# Matrix_True.net
KiCad netlist of a schematic drawn in EAGLE
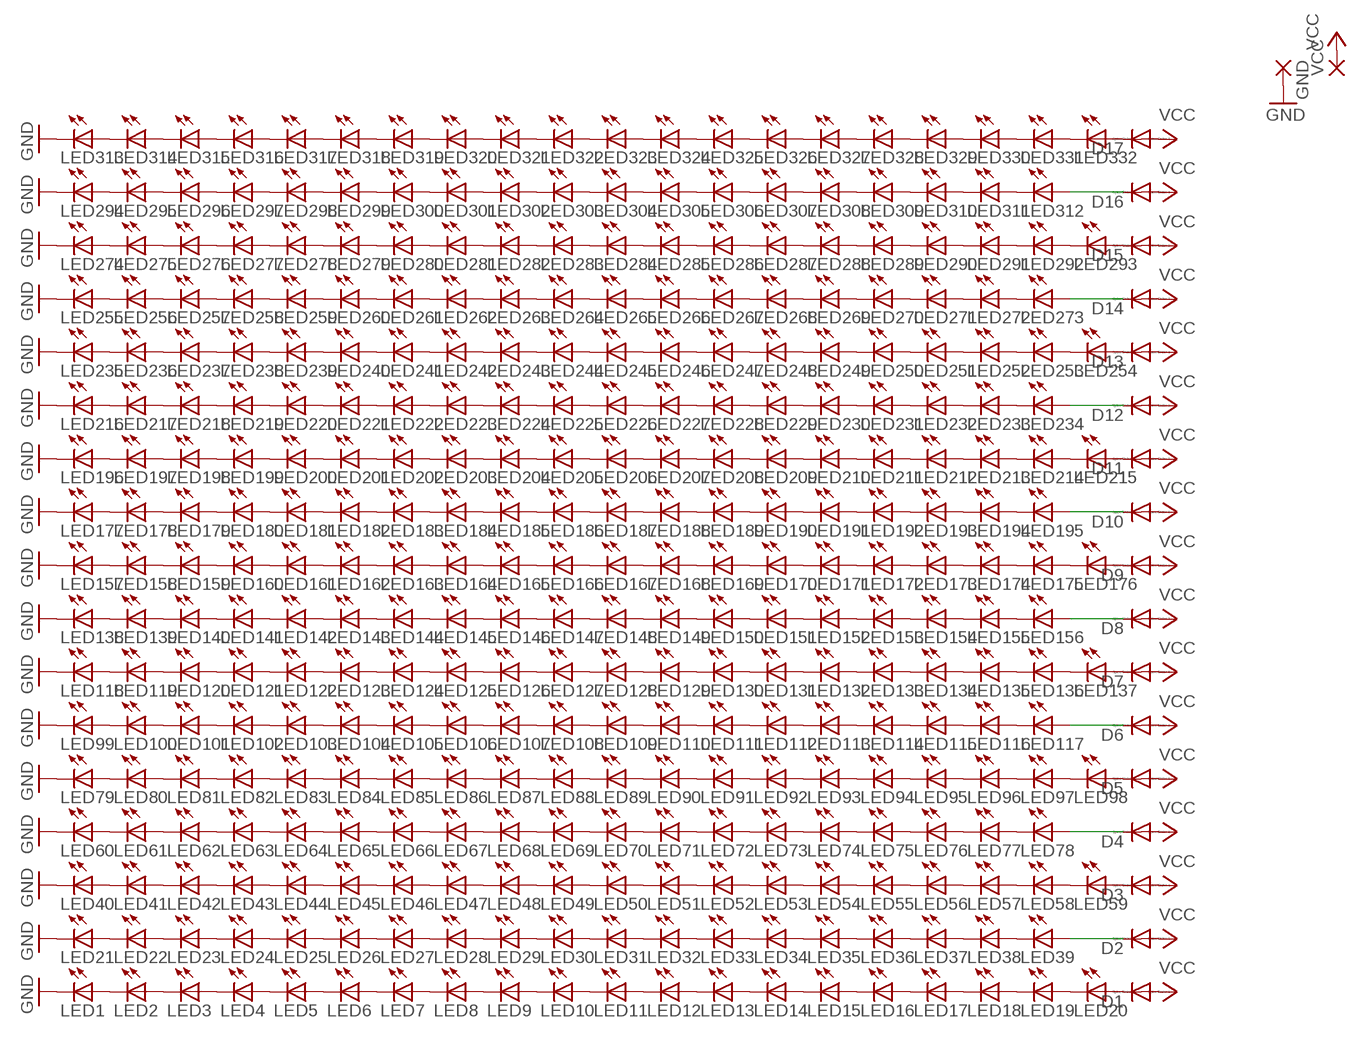
[diagram p0: schematic, sheet 1]

(export (version "E")
  (design (tool "Eeschema 10.0.6"))
  (components
    (comp (ref "D1")
      (value "DIODE-SOD123")
      (footprint "eagle-import:SOD123")
      (libsource (lib "eagle-import") (part "DIODE-SOD123"))
    )
    (comp (ref "D2")
      (value "DIODE-SOD123")
      (footprint "eagle-import:SOD123")
      (libsource (lib "eagle-import") (part "DIODE-SOD123"))
    )
    (comp (ref "D3")
      (value "DIODE-SOD123")
      (footprint "eagle-import:SOD123")
      (libsource (lib "eagle-import") (part "DIODE-SOD123"))
    )
    (comp (ref "D4")
      (value "DIODE-SOD123")
      (footprint "eagle-import:SOD123")
      (libsource (lib "eagle-import") (part "DIODE-SOD123"))
    )
    (comp (ref "D5")
      (value "DIODE-SOD123")
      (footprint "eagle-import:SOD123")
      (libsource (lib "eagle-import") (part "DIODE-SOD123"))
    )
    (comp (ref "D6")
      (value "DIODE-SOD123")
      (footprint "eagle-import:SOD123")
      (libsource (lib "eagle-import") (part "DIODE-SOD123"))
    )
    (comp (ref "D7")
      (value "DIODE-SOD123")
      (footprint "eagle-import:SOD123")
      (libsource (lib "eagle-import") (part "DIODE-SOD123"))
    )
    (comp (ref "D8")
      (value "DIODE-SOD123")
      (footprint "eagle-import:SOD123")
      (libsource (lib "eagle-import") (part "DIODE-SOD123"))
    )
    (comp (ref "D9")
      (value "DIODE-SOD123")
      (footprint "eagle-import:SOD123")
      (libsource (lib "eagle-import") (part "DIODE-SOD123"))
    )
    (comp (ref "D10")
      (value "DIODE-SOD123")
      (footprint "eagle-import:SOD123")
      (libsource (lib "eagle-import") (part "DIODE-SOD123"))
    )
    (comp (ref "D11")
      (value "DIODE-SOD123")
      (footprint "eagle-import:SOD123")
      (libsource (lib "eagle-import") (part "DIODE-SOD123"))
    )
    (comp (ref "D12")
      (value "DIODE-SOD123")
      (footprint "eagle-import:SOD123")
      (libsource (lib "eagle-import") (part "DIODE-SOD123"))
    )
    (comp (ref "D13")
      (value "DIODE-SOD123")
      (footprint "eagle-import:SOD123")
      (libsource (lib "eagle-import") (part "DIODE-SOD123"))
    )
    (comp (ref "D14")
      (value "DIODE-SOD123")
      (footprint "eagle-import:SOD123")
      (libsource (lib "eagle-import") (part "DIODE-SOD123"))
    )
    (comp (ref "D15")
      (value "DIODE-SOD123")
      (footprint "eagle-import:SOD123")
      (libsource (lib "eagle-import") (part "DIODE-SOD123"))
    )
    (comp (ref "D16")
      (value "DIODE-SOD123")
      (footprint "eagle-import:SOD123")
      (libsource (lib "eagle-import") (part "DIODE-SOD123"))
    )
    (comp (ref "D17")
      (value "DIODE-SOD123")
      (footprint "eagle-import:SOD123")
      (libsource (lib "eagle-import") (part "DIODE-SOD123"))
    )
    (comp (ref "GND")
      (value "3,17/1,3")
      (footprint "eagle-import:3,17_1,3")
      (libsource (lib "eagle-import") (part "3,17/1,3"))
    )
    (comp (ref "LED1")
      (value "LED5MM")
      (footprint "eagle-import:LED5MM")
      (libsource (lib "eagle-import") (part "LED5MM"))
    )
    (comp (ref "LED2")
      (value "LED5MM")
      (footprint "eagle-import:LED5MM")
      (libsource (lib "eagle-import") (part "LED5MM"))
    )
    (comp (ref "LED3")
      (value "LED5MM")
      (footprint "eagle-import:LED5MM")
      (libsource (lib "eagle-import") (part "LED5MM"))
    )
    (comp (ref "LED4")
      (value "LED5MM")
      (footprint "eagle-import:LED5MM")
      (libsource (lib "eagle-import") (part "LED5MM"))
    )
    (comp (ref "LED5")
      (value "LED5MM")
      (footprint "eagle-import:LED5MM")
      (libsource (lib "eagle-import") (part "LED5MM"))
    )
    (comp (ref "LED6")
      (value "LED5MM")
      (footprint "eagle-import:LED5MM")
      (libsource (lib "eagle-import") (part "LED5MM"))
    )
    (comp (ref "LED7")
      (value "LED5MM")
      (footprint "eagle-import:LED5MM")
      (libsource (lib "eagle-import") (part "LED5MM"))
    )
    (comp (ref "LED8")
      (value "LED5MM")
      (footprint "eagle-import:LED5MM")
      (libsource (lib "eagle-import") (part "LED5MM"))
    )
    (comp (ref "LED9")
      (value "LED5MM")
      (footprint "eagle-import:LED5MM")
      (libsource (lib "eagle-import") (part "LED5MM"))
    )
    (comp (ref "LED10")
      (value "LED5MM")
      (footprint "eagle-import:LED5MM")
      (libsource (lib "eagle-import") (part "LED5MM"))
    )
    (comp (ref "LED11")
      (value "LED5MM")
      (footprint "eagle-import:LED5MM")
      (libsource (lib "eagle-import") (part "LED5MM"))
    )
    (comp (ref "LED12")
      (value "LED5MM")
      (footprint "eagle-import:LED5MM")
      (libsource (lib "eagle-import") (part "LED5MM"))
    )
    (comp (ref "LED13")
      (value "LED5MM")
      (footprint "eagle-import:LED5MM")
      (libsource (lib "eagle-import") (part "LED5MM"))
    )
    (comp (ref "LED14")
      (value "LED5MM")
      (footprint "eagle-import:LED5MM")
      (libsource (lib "eagle-import") (part "LED5MM"))
    )
    (comp (ref "LED15")
      (value "LED5MM")
      (footprint "eagle-import:LED5MM")
      (libsource (lib "eagle-import") (part "LED5MM"))
    )
    (comp (ref "LED16")
      (value "LED5MM")
      (footprint "eagle-import:LED5MM")
      (libsource (lib "eagle-import") (part "LED5MM"))
    )
    (comp (ref "LED17")
      (value "LED5MM")
      (footprint "eagle-import:LED5MM")
      (libsource (lib "eagle-import") (part "LED5MM"))
    )
    (comp (ref "LED18")
      (value "LED5MM")
      (footprint "eagle-import:LED5MM")
      (libsource (lib "eagle-import") (part "LED5MM"))
    )
    (comp (ref "LED19")
      (value "LED5MM")
      (footprint "eagle-import:LED5MM")
      (libsource (lib "eagle-import") (part "LED5MM"))
    )
    (comp (ref "LED20")
      (value "LED5MM")
      (footprint "eagle-import:LED5MM")
      (libsource (lib "eagle-import") (part "LED5MM"))
    )
    (comp (ref "LED21")
      (value "LED5MM")
      (footprint "eagle-import:LED5MM")
      (libsource (lib "eagle-import") (part "LED5MM"))
    )
    (comp (ref "LED22")
      (value "LED5MM")
      (footprint "eagle-import:LED5MM")
      (libsource (lib "eagle-import") (part "LED5MM"))
    )
    (comp (ref "LED23")
      (value "LED5MM")
      (footprint "eagle-import:LED5MM")
      (libsource (lib "eagle-import") (part "LED5MM"))
    )
    (comp (ref "LED24")
      (value "LED5MM")
      (footprint "eagle-import:LED5MM")
      (libsource (lib "eagle-import") (part "LED5MM"))
    )
    (comp (ref "LED25")
      (value "LED5MM")
      (footprint "eagle-import:LED5MM")
      (libsource (lib "eagle-import") (part "LED5MM"))
    )
    (comp (ref "LED26")
      (value "LED5MM")
      (footprint "eagle-import:LED5MM")
      (libsource (lib "eagle-import") (part "LED5MM"))
    )
    (comp (ref "LED27")
      (value "LED5MM")
      (footprint "eagle-import:LED5MM")
      (libsource (lib "eagle-import") (part "LED5MM"))
    )
    (comp (ref "LED28")
      (value "LED5MM")
      (footprint "eagle-import:LED5MM")
      (libsource (lib "eagle-import") (part "LED5MM"))
    )
    (comp (ref "LED29")
      (value "LED5MM")
      (footprint "eagle-import:LED5MM")
      (libsource (lib "eagle-import") (part "LED5MM"))
    )
    (comp (ref "LED30")
      (value "LED5MM")
      (footprint "eagle-import:LED5MM")
      (libsource (lib "eagle-import") (part "LED5MM"))
    )
    (comp (ref "LED31")
      (value "LED5MM")
      (footprint "eagle-import:LED5MM")
      (libsource (lib "eagle-import") (part "LED5MM"))
    )
    (comp (ref "LED32")
      (value "LED5MM")
      (footprint "eagle-import:LED5MM")
      (libsource (lib "eagle-import") (part "LED5MM"))
    )
    (comp (ref "LED33")
      (value "LED5MM")
      (footprint "eagle-import:LED5MM")
      (libsource (lib "eagle-import") (part "LED5MM"))
    )
    (comp (ref "LED34")
      (value "LED5MM")
      (footprint "eagle-import:LED5MM")
      (libsource (lib "eagle-import") (part "LED5MM"))
    )
    (comp (ref "LED35")
      (value "LED5MM")
      (footprint "eagle-import:LED5MM")
      (libsource (lib "eagle-import") (part "LED5MM"))
    )
    (comp (ref "LED36")
      (value "LED5MM")
      (footprint "eagle-import:LED5MM")
      (libsource (lib "eagle-import") (part "LED5MM"))
    )
    (comp (ref "LED37")
      (value "LED5MM")
      (footprint "eagle-import:LED5MM")
      (libsource (lib "eagle-import") (part "LED5MM"))
    )
    (comp (ref "LED38")
      (value "LED5MM")
      (footprint "eagle-import:LED5MM")
      (libsource (lib "eagle-import") (part "LED5MM"))
    )
    (comp (ref "LED39")
      (value "LED5MM")
      (footprint "eagle-import:LED5MM")
      (libsource (lib "eagle-import") (part "LED5MM"))
    )
    (comp (ref "LED40")
      (value "LED5MM")
      (footprint "eagle-import:LED5MM")
      (libsource (lib "eagle-import") (part "LED5MM"))
    )
    (comp (ref "LED41")
      (value "LED5MM")
      (footprint "eagle-import:LED5MM")
      (libsource (lib "eagle-import") (part "LED5MM"))
    )
    (comp (ref "LED42")
      (value "LED5MM")
      (footprint "eagle-import:LED5MM")
      (libsource (lib "eagle-import") (part "LED5MM"))
    )
    (comp (ref "LED43")
      (value "LED5MM")
      (footprint "eagle-import:LED5MM")
      (libsource (lib "eagle-import") (part "LED5MM"))
    )
    (comp (ref "LED44")
      (value "LED5MM")
      (footprint "eagle-import:LED5MM")
      (libsource (lib "eagle-import") (part "LED5MM"))
    )
    (comp (ref "LED45")
      (value "LED5MM")
      (footprint "eagle-import:LED5MM")
      (libsource (lib "eagle-import") (part "LED5MM"))
    )
    (comp (ref "LED46")
      (value "LED5MM")
      (footprint "eagle-import:LED5MM")
      (libsource (lib "eagle-import") (part "LED5MM"))
    )
    (comp (ref "LED47")
      (value "LED5MM")
      (footprint "eagle-import:LED5MM")
      (libsource (lib "eagle-import") (part "LED5MM"))
    )
    (comp (ref "LED48")
      (value "LED5MM")
      (footprint "eagle-import:LED5MM")
      (libsource (lib "eagle-import") (part "LED5MM"))
    )
    (comp (ref "LED49")
      (value "LED5MM")
      (footprint "eagle-import:LED5MM")
      (libsource (lib "eagle-import") (part "LED5MM"))
    )
    (comp (ref "LED50")
      (value "LED5MM")
      (footprint "eagle-import:LED5MM")
      (libsource (lib "eagle-import") (part "LED5MM"))
    )
    (comp (ref "LED51")
      (value "LED5MM")
      (footprint "eagle-import:LED5MM")
      (libsource (lib "eagle-import") (part "LED5MM"))
    )
    (comp (ref "LED52")
      (value "LED5MM")
      (footprint "eagle-import:LED5MM")
      (libsource (lib "eagle-import") (part "LED5MM"))
    )
    (comp (ref "LED53")
      (value "LED5MM")
      (footprint "eagle-import:LED5MM")
      (libsource (lib "eagle-import") (part "LED5MM"))
    )
    (comp (ref "LED54")
      (value "LED5MM")
      (footprint "eagle-import:LED5MM")
      (libsource (lib "eagle-import") (part "LED5MM"))
    )
    (comp (ref "LED55")
      (value "LED5MM")
      (footprint "eagle-import:LED5MM")
      (libsource (lib "eagle-import") (part "LED5MM"))
    )
    (comp (ref "LED56")
      (value "LED5MM")
      (footprint "eagle-import:LED5MM")
      (libsource (lib "eagle-import") (part "LED5MM"))
    )
    (comp (ref "LED57")
      (value "LED5MM")
      (footprint "eagle-import:LED5MM")
      (libsource (lib "eagle-import") (part "LED5MM"))
    )
    (comp (ref "LED58")
      (value "LED5MM")
      (footprint "eagle-import:LED5MM")
      (libsource (lib "eagle-import") (part "LED5MM"))
    )
    (comp (ref "LED59")
      (value "LED5MM")
      (footprint "eagle-import:LED5MM")
      (libsource (lib "eagle-import") (part "LED5MM"))
    )
    (comp (ref "LED60")
      (value "LED5MM")
      (footprint "eagle-import:LED5MM")
      (libsource (lib "eagle-import") (part "LED5MM"))
    )
    (comp (ref "LED61")
      (value "LED5MM")
      (footprint "eagle-import:LED5MM")
      (libsource (lib "eagle-import") (part "LED5MM"))
    )
    (comp (ref "LED62")
      (value "LED5MM")
      (footprint "eagle-import:LED5MM")
      (libsource (lib "eagle-import") (part "LED5MM"))
    )
    (comp (ref "LED63")
      (value "LED5MM")
      (footprint "eagle-import:LED5MM")
      (libsource (lib "eagle-import") (part "LED5MM"))
    )
    (comp (ref "LED64")
      (value "LED5MM")
      (footprint "eagle-import:LED5MM")
      (libsource (lib "eagle-import") (part "LED5MM"))
    )
    (comp (ref "LED65")
      (value "LED5MM")
      (footprint "eagle-import:LED5MM")
      (libsource (lib "eagle-import") (part "LED5MM"))
    )
    (comp (ref "LED66")
      (value "LED5MM")
      (footprint "eagle-import:LED5MM")
      (libsource (lib "eagle-import") (part "LED5MM"))
    )
    (comp (ref "LED67")
      (value "LED5MM")
      (footprint "eagle-import:LED5MM")
      (libsource (lib "eagle-import") (part "LED5MM"))
    )
    (comp (ref "LED68")
      (value "LED5MM")
      (footprint "eagle-import:LED5MM")
      (libsource (lib "eagle-import") (part "LED5MM"))
    )
    (comp (ref "LED69")
      (value "LED5MM")
      (footprint "eagle-import:LED5MM")
      (libsource (lib "eagle-import") (part "LED5MM"))
    )
    (comp (ref "LED70")
      (value "LED5MM")
      (footprint "eagle-import:LED5MM")
      (libsource (lib "eagle-import") (part "LED5MM"))
    )
    (comp (ref "LED71")
      (value "LED5MM")
      (footprint "eagle-import:LED5MM")
      (libsource (lib "eagle-import") (part "LED5MM"))
    )
    (comp (ref "LED72")
      (value "LED5MM")
      (footprint "eagle-import:LED5MM")
      (libsource (lib "eagle-import") (part "LED5MM"))
    )
    (comp (ref "LED73")
      (value "LED5MM")
      (footprint "eagle-import:LED5MM")
      (libsource (lib "eagle-import") (part "LED5MM"))
    )
    (comp (ref "LED74")
      (value "LED5MM")
      (footprint "eagle-import:LED5MM")
      (libsource (lib "eagle-import") (part "LED5MM"))
    )
    (comp (ref "LED75")
      (value "LED5MM")
      (footprint "eagle-import:LED5MM")
      (libsource (lib "eagle-import") (part "LED5MM"))
    )
    (comp (ref "LED76")
      (value "LED5MM")
      (footprint "eagle-import:LED5MM")
      (libsource (lib "eagle-import") (part "LED5MM"))
    )
    (comp (ref "LED77")
      (value "LED5MM")
      (footprint "eagle-import:LED5MM")
      (libsource (lib "eagle-import") (part "LED5MM"))
    )
    (comp (ref "LED78")
      (value "LED5MM")
      (footprint "eagle-import:LED5MM")
      (libsource (lib "eagle-import") (part "LED5MM"))
    )
    (comp (ref "LED79")
      (value "LED5MM")
      (footprint "eagle-import:LED5MM")
      (libsource (lib "eagle-import") (part "LED5MM"))
    )
    (comp (ref "LED80")
      (value "LED5MM")
      (footprint "eagle-import:LED5MM")
      (libsource (lib "eagle-import") (part "LED5MM"))
    )
    (comp (ref "LED81")
      (value "LED5MM")
      (footprint "eagle-import:LED5MM")
      (libsource (lib "eagle-import") (part "LED5MM"))
    )
    (comp (ref "LED82")
      (value "LED5MM")
      (footprint "eagle-import:LED5MM")
      (libsource (lib "eagle-import") (part "LED5MM"))
    )
    (comp (ref "LED83")
      (value "LED5MM")
      (footprint "eagle-import:LED5MM")
      (libsource (lib "eagle-import") (part "LED5MM"))
    )
    (comp (ref "LED84")
      (value "LED5MM")
      (footprint "eagle-import:LED5MM")
      (libsource (lib "eagle-import") (part "LED5MM"))
    )
    (comp (ref "LED85")
      (value "LED5MM")
      (footprint "eagle-import:LED5MM")
      (libsource (lib "eagle-import") (part "LED5MM"))
    )
    (comp (ref "LED86")
      (value "LED5MM")
      (footprint "eagle-import:LED5MM")
      (libsource (lib "eagle-import") (part "LED5MM"))
    )
    (comp (ref "LED87")
      (value "LED5MM")
      (footprint "eagle-import:LED5MM")
      (libsource (lib "eagle-import") (part "LED5MM"))
    )
    (comp (ref "LED88")
      (value "LED5MM")
      (footprint "eagle-import:LED5MM")
      (libsource (lib "eagle-import") (part "LED5MM"))
    )
    (comp (ref "LED89")
      (value "LED5MM")
      (footprint "eagle-import:LED5MM")
      (libsource (lib "eagle-import") (part "LED5MM"))
    )
    (comp (ref "LED90")
      (value "LED5MM")
      (footprint "eagle-import:LED5MM")
      (libsource (lib "eagle-import") (part "LED5MM"))
    )
    (comp (ref "LED91")
      (value "LED5MM")
      (footprint "eagle-import:LED5MM")
      (libsource (lib "eagle-import") (part "LED5MM"))
    )
    (comp (ref "LED92")
      (value "LED5MM")
      (footprint "eagle-import:LED5MM")
      (libsource (lib "eagle-import") (part "LED5MM"))
    )
    (comp (ref "LED93")
      (value "LED5MM")
      (footprint "eagle-import:LED5MM")
      (libsource (lib "eagle-import") (part "LED5MM"))
    )
    (comp (ref "LED94")
      (value "LED5MM")
      (footprint "eagle-import:LED5MM")
      (libsource (lib "eagle-import") (part "LED5MM"))
    )
    (comp (ref "LED95")
      (value "LED5MM")
      (footprint "eagle-import:LED5MM")
      (libsource (lib "eagle-import") (part "LED5MM"))
    )
    (comp (ref "LED96")
      (value "LED5MM")
      (footprint "eagle-import:LED5MM")
      (libsource (lib "eagle-import") (part "LED5MM"))
    )
    (comp (ref "LED97")
      (value "LED5MM")
      (footprint "eagle-import:LED5MM")
      (libsource (lib "eagle-import") (part "LED5MM"))
    )
    (comp (ref "LED98")
      (value "LED5MM")
      (footprint "eagle-import:LED5MM")
      (libsource (lib "eagle-import") (part "LED5MM"))
    )
    (comp (ref "LED99")
      (value "LED5MM")
      (footprint "eagle-import:LED5MM")
      (libsource (lib "eagle-import") (part "LED5MM"))
    )
    (comp (ref "LED100")
      (value "LED5MM")
      (footprint "eagle-import:LED5MM")
      (libsource (lib "eagle-import") (part "LED5MM"))
    )
    (comp (ref "LED101")
      (value "LED5MM")
      (footprint "eagle-import:LED5MM")
      (libsource (lib "eagle-import") (part "LED5MM"))
    )
    (comp (ref "LED102")
      (value "LED5MM")
      (footprint "eagle-import:LED5MM")
      (libsource (lib "eagle-import") (part "LED5MM"))
    )
    (comp (ref "LED103")
      (value "LED5MM")
      (footprint "eagle-import:LED5MM")
      (libsource (lib "eagle-import") (part "LED5MM"))
    )
    (comp (ref "LED104")
      (value "LED5MM")
      (footprint "eagle-import:LED5MM")
      (libsource (lib "eagle-import") (part "LED5MM"))
    )
    (comp (ref "LED105")
      (value "LED5MM")
      (footprint "eagle-import:LED5MM")
      (libsource (lib "eagle-import") (part "LED5MM"))
    )
    (comp (ref "LED106")
      (value "LED5MM")
      (footprint "eagle-import:LED5MM")
      (libsource (lib "eagle-import") (part "LED5MM"))
    )
    (comp (ref "LED107")
      (value "LED5MM")
      (footprint "eagle-import:LED5MM")
      (libsource (lib "eagle-import") (part "LED5MM"))
    )
    (comp (ref "LED108")
      (value "LED5MM")
      (footprint "eagle-import:LED5MM")
      (libsource (lib "eagle-import") (part "LED5MM"))
    )
    (comp (ref "LED109")
      (value "LED5MM")
      (footprint "eagle-import:LED5MM")
      (libsource (lib "eagle-import") (part "LED5MM"))
    )
    (comp (ref "LED110")
      (value "LED5MM")
      (footprint "eagle-import:LED5MM")
      (libsource (lib "eagle-import") (part "LED5MM"))
    )
    (comp (ref "LED111")
      (value "LED5MM")
      (footprint "eagle-import:LED5MM")
      (libsource (lib "eagle-import") (part "LED5MM"))
    )
    (comp (ref "LED112")
      (value "LED5MM")
      (footprint "eagle-import:LED5MM")
      (libsource (lib "eagle-import") (part "LED5MM"))
    )
    (comp (ref "LED113")
      (value "LED5MM")
      (footprint "eagle-import:LED5MM")
      (libsource (lib "eagle-import") (part "LED5MM"))
    )
    (comp (ref "LED114")
      (value "LED5MM")
      (footprint "eagle-import:LED5MM")
      (libsource (lib "eagle-import") (part "LED5MM"))
    )
    (comp (ref "LED115")
      (value "LED5MM")
      (footprint "eagle-import:LED5MM")
      (libsource (lib "eagle-import") (part "LED5MM"))
    )
    (comp (ref "LED116")
      (value "LED5MM")
      (footprint "eagle-import:LED5MM")
      (libsource (lib "eagle-import") (part "LED5MM"))
    )
    (comp (ref "LED117")
      (value "LED5MM")
      (footprint "eagle-import:LED5MM")
      (libsource (lib "eagle-import") (part "LED5MM"))
    )
    (comp (ref "LED118")
      (value "LED5MM")
      (footprint "eagle-import:LED5MM")
      (libsource (lib "eagle-import") (part "LED5MM"))
    )
    (comp (ref "LED119")
      (value "LED5MM")
      (footprint "eagle-import:LED5MM")
      (libsource (lib "eagle-import") (part "LED5MM"))
    )
    (comp (ref "LED120")
      (value "LED5MM")
      (footprint "eagle-import:LED5MM")
      (libsource (lib "eagle-import") (part "LED5MM"))
    )
    (comp (ref "LED121")
      (value "LED5MM")
      (footprint "eagle-import:LED5MM")
      (libsource (lib "eagle-import") (part "LED5MM"))
    )
    (comp (ref "LED122")
      (value "LED5MM")
      (footprint "eagle-import:LED5MM")
      (libsource (lib "eagle-import") (part "LED5MM"))
    )
    (comp (ref "LED123")
      (value "LED5MM")
      (footprint "eagle-import:LED5MM")
      (libsource (lib "eagle-import") (part "LED5MM"))
    )
    (comp (ref "LED124")
      (value "LED5MM")
      (footprint "eagle-import:LED5MM")
      (libsource (lib "eagle-import") (part "LED5MM"))
    )
    (comp (ref "LED125")
      (value "LED5MM")
      (footprint "eagle-import:LED5MM")
      (libsource (lib "eagle-import") (part "LED5MM"))
    )
    (comp (ref "LED126")
      (value "LED5MM")
      (footprint "eagle-import:LED5MM")
      (libsource (lib "eagle-import") (part "LED5MM"))
    )
    (comp (ref "LED127")
      (value "LED5MM")
      (footprint "eagle-import:LED5MM")
      (libsource (lib "eagle-import") (part "LED5MM"))
    )
    (comp (ref "LED128")
      (value "LED5MM")
      (footprint "eagle-import:LED5MM")
      (libsource (lib "eagle-import") (part "LED5MM"))
    )
    (comp (ref "LED129")
      (value "LED5MM")
      (footprint "eagle-import:LED5MM")
      (libsource (lib "eagle-import") (part "LED5MM"))
    )
    (comp (ref "LED130")
      (value "LED5MM")
      (footprint "eagle-import:LED5MM")
      (libsource (lib "eagle-import") (part "LED5MM"))
    )
    (comp (ref "LED131")
      (value "LED5MM")
      (footprint "eagle-import:LED5MM")
      (libsource (lib "eagle-import") (part "LED5MM"))
    )
    (comp (ref "LED132")
      (value "LED5MM")
      (footprint "eagle-import:LED5MM")
      (libsource (lib "eagle-import") (part "LED5MM"))
    )
    (comp (ref "LED133")
      (value "LED5MM")
      (footprint "eagle-import:LED5MM")
      (libsource (lib "eagle-import") (part "LED5MM"))
    )
    (comp (ref "LED134")
      (value "LED5MM")
      (footprint "eagle-import:LED5MM")
      (libsource (lib "eagle-import") (part "LED5MM"))
    )
    (comp (ref "LED135")
      (value "LED5MM")
      (footprint "eagle-import:LED5MM")
      (libsource (lib "eagle-import") (part "LED5MM"))
    )
    (comp (ref "LED136")
      (value "LED5MM")
      (footprint "eagle-import:LED5MM")
      (libsource (lib "eagle-import") (part "LED5MM"))
    )
    (comp (ref "LED137")
      (value "LED5MM")
      (footprint "eagle-import:LED5MM")
      (libsource (lib "eagle-import") (part "LED5MM"))
    )
    (comp (ref "LED138")
      (value "LED5MM")
      (footprint "eagle-import:LED5MM")
      (libsource (lib "eagle-import") (part "LED5MM"))
    )
    (comp (ref "LED139")
      (value "LED5MM")
      (footprint "eagle-import:LED5MM")
      (libsource (lib "eagle-import") (part "LED5MM"))
    )
    (comp (ref "LED140")
      (value "LED5MM")
      (footprint "eagle-import:LED5MM")
      (libsource (lib "eagle-import") (part "LED5MM"))
    )
    (comp (ref "LED141")
      (value "LED5MM")
      (footprint "eagle-import:LED5MM")
      (libsource (lib "eagle-import") (part "LED5MM"))
    )
    (comp (ref "LED142")
      (value "LED5MM")
      (footprint "eagle-import:LED5MM")
      (libsource (lib "eagle-import") (part "LED5MM"))
    )
    (comp (ref "LED143")
      (value "LED5MM")
      (footprint "eagle-import:LED5MM")
      (libsource (lib "eagle-import") (part "LED5MM"))
    )
    (comp (ref "LED144")
      (value "LED5MM")
      (footprint "eagle-import:LED5MM")
      (libsource (lib "eagle-import") (part "LED5MM"))
    )
    (comp (ref "LED145")
      (value "LED5MM")
      (footprint "eagle-import:LED5MM")
      (libsource (lib "eagle-import") (part "LED5MM"))
    )
    (comp (ref "LED146")
      (value "LED5MM")
      (footprint "eagle-import:LED5MM")
      (libsource (lib "eagle-import") (part "LED5MM"))
    )
    (comp (ref "LED147")
      (value "LED5MM")
      (footprint "eagle-import:LED5MM")
      (libsource (lib "eagle-import") (part "LED5MM"))
    )
    (comp (ref "LED148")
      (value "LED5MM")
      (footprint "eagle-import:LED5MM")
      (libsource (lib "eagle-import") (part "LED5MM"))
    )
    (comp (ref "LED149")
      (value "LED5MM")
      (footprint "eagle-import:LED5MM")
      (libsource (lib "eagle-import") (part "LED5MM"))
    )
    (comp (ref "LED150")
      (value "LED5MM")
      (footprint "eagle-import:LED5MM")
      (libsource (lib "eagle-import") (part "LED5MM"))
    )
    (comp (ref "LED151")
      (value "LED5MM")
      (footprint "eagle-import:LED5MM")
      (libsource (lib "eagle-import") (part "LED5MM"))
    )
    (comp (ref "LED152")
      (value "LED5MM")
      (footprint "eagle-import:LED5MM")
      (libsource (lib "eagle-import") (part "LED5MM"))
    )
    (comp (ref "LED153")
      (value "LED5MM")
      (footprint "eagle-import:LED5MM")
      (libsource (lib "eagle-import") (part "LED5MM"))
    )
    (comp (ref "LED154")
      (value "LED5MM")
      (footprint "eagle-import:LED5MM")
      (libsource (lib "eagle-import") (part "LED5MM"))
    )
    (comp (ref "LED155")
      (value "LED5MM")
      (footprint "eagle-import:LED5MM")
      (libsource (lib "eagle-import") (part "LED5MM"))
    )
    (comp (ref "LED156")
      (value "LED5MM")
      (footprint "eagle-import:LED5MM")
      (libsource (lib "eagle-import") (part "LED5MM"))
    )
    (comp (ref "LED157")
      (value "LED5MM")
      (footprint "eagle-import:LED5MM")
      (libsource (lib "eagle-import") (part "LED5MM"))
    )
    (comp (ref "LED158")
      (value "LED5MM")
      (footprint "eagle-import:LED5MM")
      (libsource (lib "eagle-import") (part "LED5MM"))
    )
    (comp (ref "LED159")
      (value "LED5MM")
      (footprint "eagle-import:LED5MM")
      (libsource (lib "eagle-import") (part "LED5MM"))
    )
    (comp (ref "LED160")
      (value "LED5MM")
      (footprint "eagle-import:LED5MM")
      (libsource (lib "eagle-import") (part "LED5MM"))
    )
    (comp (ref "LED161")
      (value "LED5MM")
      (footprint "eagle-import:LED5MM")
      (libsource (lib "eagle-import") (part "LED5MM"))
    )
    (comp (ref "LED162")
      (value "LED5MM")
      (footprint "eagle-import:LED5MM")
      (libsource (lib "eagle-import") (part "LED5MM"))
    )
    (comp (ref "LED163")
      (value "LED5MM")
      (footprint "eagle-import:LED5MM")
      (libsource (lib "eagle-import") (part "LED5MM"))
    )
    (comp (ref "LED164")
      (value "LED5MM")
      (footprint "eagle-import:LED5MM")
      (libsource (lib "eagle-import") (part "LED5MM"))
    )
    (comp (ref "LED165")
      (value "LED5MM")
      (footprint "eagle-import:LED5MM")
      (libsource (lib "eagle-import") (part "LED5MM"))
    )
    (comp (ref "LED166")
      (value "LED5MM")
      (footprint "eagle-import:LED5MM")
      (libsource (lib "eagle-import") (part "LED5MM"))
    )
    (comp (ref "LED167")
      (value "LED5MM")
      (footprint "eagle-import:LED5MM")
      (libsource (lib "eagle-import") (part "LED5MM"))
    )
    (comp (ref "LED168")
      (value "LED5MM")
      (footprint "eagle-import:LED5MM")
      (libsource (lib "eagle-import") (part "LED5MM"))
    )
    (comp (ref "LED169")
      (value "LED5MM")
      (footprint "eagle-import:LED5MM")
      (libsource (lib "eagle-import") (part "LED5MM"))
    )
    (comp (ref "LED170")
      (value "LED5MM")
      (footprint "eagle-import:LED5MM")
      (libsource (lib "eagle-import") (part "LED5MM"))
    )
    (comp (ref "LED171")
      (value "LED5MM")
      (footprint "eagle-import:LED5MM")
      (libsource (lib "eagle-import") (part "LED5MM"))
    )
    (comp (ref "LED172")
      (value "LED5MM")
      (footprint "eagle-import:LED5MM")
      (libsource (lib "eagle-import") (part "LED5MM"))
    )
    (comp (ref "LED173")
      (value "LED5MM")
      (footprint "eagle-import:LED5MM")
      (libsource (lib "eagle-import") (part "LED5MM"))
    )
    (comp (ref "LED174")
      (value "LED5MM")
      (footprint "eagle-import:LED5MM")
      (libsource (lib "eagle-import") (part "LED5MM"))
    )
    (comp (ref "LED175")
      (value "LED5MM")
      (footprint "eagle-import:LED5MM")
      (libsource (lib "eagle-import") (part "LED5MM"))
    )
    (comp (ref "LED176")
      (value "LED5MM")
      (footprint "eagle-import:LED5MM")
      (libsource (lib "eagle-import") (part "LED5MM"))
    )
    (comp (ref "LED177")
      (value "LED5MM")
      (footprint "eagle-import:LED5MM")
      (libsource (lib "eagle-import") (part "LED5MM"))
    )
    (comp (ref "LED178")
      (value "LED5MM")
      (footprint "eagle-import:LED5MM")
      (libsource (lib "eagle-import") (part "LED5MM"))
    )
    (comp (ref "LED179")
      (value "LED5MM")
      (footprint "eagle-import:LED5MM")
      (libsource (lib "eagle-import") (part "LED5MM"))
    )
    (comp (ref "LED180")
      (value "LED5MM")
      (footprint "eagle-import:LED5MM")
      (libsource (lib "eagle-import") (part "LED5MM"))
    )
    (comp (ref "LED181")
      (value "LED5MM")
      (footprint "eagle-import:LED5MM")
      (libsource (lib "eagle-import") (part "LED5MM"))
    )
    (comp (ref "LED182")
      (value "LED5MM")
      (footprint "eagle-import:LED5MM")
      (libsource (lib "eagle-import") (part "LED5MM"))
    )
    (comp (ref "LED183")
      (value "LED5MM")
      (footprint "eagle-import:LED5MM")
      (libsource (lib "eagle-import") (part "LED5MM"))
    )
    (comp (ref "LED184")
      (value "LED5MM")
      (footprint "eagle-import:LED5MM")
      (libsource (lib "eagle-import") (part "LED5MM"))
    )
    (comp (ref "LED185")
      (value "LED5MM")
      (footprint "eagle-import:LED5MM")
      (libsource (lib "eagle-import") (part "LED5MM"))
    )
    (comp (ref "LED186")
      (value "LED5MM")
      (footprint "eagle-import:LED5MM")
      (libsource (lib "eagle-import") (part "LED5MM"))
    )
    (comp (ref "LED187")
      (value "LED5MM")
      (footprint "eagle-import:LED5MM")
      (libsource (lib "eagle-import") (part "LED5MM"))
    )
    (comp (ref "LED188")
      (value "LED5MM")
      (footprint "eagle-import:LED5MM")
      (libsource (lib "eagle-import") (part "LED5MM"))
    )
    (comp (ref "LED189")
      (value "LED5MM")
      (footprint "eagle-import:LED5MM")
      (libsource (lib "eagle-import") (part "LED5MM"))
    )
    (comp (ref "LED190")
      (value "LED5MM")
      (footprint "eagle-import:LED5MM")
      (libsource (lib "eagle-import") (part "LED5MM"))
    )
    (comp (ref "LED191")
      (value "LED5MM")
      (footprint "eagle-import:LED5MM")
      (libsource (lib "eagle-import") (part "LED5MM"))
    )
    (comp (ref "LED192")
      (value "LED5MM")
      (footprint "eagle-import:LED5MM")
      (libsource (lib "eagle-import") (part "LED5MM"))
    )
    (comp (ref "LED193")
      (value "LED5MM")
      (footprint "eagle-import:LED5MM")
      (libsource (lib "eagle-import") (part "LED5MM"))
    )
    (comp (ref "LED194")
      (value "LED5MM")
      (footprint "eagle-import:LED5MM")
      (libsource (lib "eagle-import") (part "LED5MM"))
    )
    (comp (ref "LED195")
      (value "LED5MM")
      (footprint "eagle-import:LED5MM")
      (libsource (lib "eagle-import") (part "LED5MM"))
    )
    (comp (ref "LED196")
      (value "LED5MM")
      (footprint "eagle-import:LED5MM")
      (libsource (lib "eagle-import") (part "LED5MM"))
    )
    (comp (ref "LED197")
      (value "LED5MM")
      (footprint "eagle-import:LED5MM")
      (libsource (lib "eagle-import") (part "LED5MM"))
    )
    (comp (ref "LED198")
      (value "LED5MM")
      (footprint "eagle-import:LED5MM")
      (libsource (lib "eagle-import") (part "LED5MM"))
    )
    (comp (ref "LED199")
      (value "LED5MM")
      (footprint "eagle-import:LED5MM")
      (libsource (lib "eagle-import") (part "LED5MM"))
    )
    (comp (ref "LED200")
      (value "LED5MM")
      (footprint "eagle-import:LED5MM")
      (libsource (lib "eagle-import") (part "LED5MM"))
    )
    (comp (ref "LED201")
      (value "LED5MM")
      (footprint "eagle-import:LED5MM")
      (libsource (lib "eagle-import") (part "LED5MM"))
    )
    (comp (ref "LED202")
      (value "LED5MM")
      (footprint "eagle-import:LED5MM")
      (libsource (lib "eagle-import") (part "LED5MM"))
    )
    (comp (ref "LED203")
      (value "LED5MM")
      (footprint "eagle-import:LED5MM")
      (libsource (lib "eagle-import") (part "LED5MM"))
    )
    (comp (ref "LED204")
      (value "LED5MM")
      (footprint "eagle-import:LED5MM")
      (libsource (lib "eagle-import") (part "LED5MM"))
    )
    (comp (ref "LED205")
      (value "LED5MM")
      (footprint "eagle-import:LED5MM")
      (libsource (lib "eagle-import") (part "LED5MM"))
    )
    (comp (ref "LED206")
      (value "LED5MM")
      (footprint "eagle-import:LED5MM")
      (libsource (lib "eagle-import") (part "LED5MM"))
    )
    (comp (ref "LED207")
      (value "LED5MM")
      (footprint "eagle-import:LED5MM")
      (libsource (lib "eagle-import") (part "LED5MM"))
    )
    (comp (ref "LED208")
      (value "LED5MM")
      (footprint "eagle-import:LED5MM")
      (libsource (lib "eagle-import") (part "LED5MM"))
    )
    (comp (ref "LED209")
      (value "LED5MM")
      (footprint "eagle-import:LED5MM")
      (libsource (lib "eagle-import") (part "LED5MM"))
    )
    (comp (ref "LED210")
      (value "LED5MM")
      (footprint "eagle-import:LED5MM")
      (libsource (lib "eagle-import") (part "LED5MM"))
    )
    (comp (ref "LED211")
      (value "LED5MM")
      (footprint "eagle-import:LED5MM")
      (libsource (lib "eagle-import") (part "LED5MM"))
    )
    (comp (ref "LED212")
      (value "LED5MM")
      (footprint "eagle-import:LED5MM")
      (libsource (lib "eagle-import") (part "LED5MM"))
    )
    (comp (ref "LED213")
      (value "LED5MM")
      (footprint "eagle-import:LED5MM")
      (libsource (lib "eagle-import") (part "LED5MM"))
    )
    (comp (ref "LED214")
      (value "LED5MM")
      (footprint "eagle-import:LED5MM")
      (libsource (lib "eagle-import") (part "LED5MM"))
    )
    (comp (ref "LED215")
      (value "LED5MM")
      (footprint "eagle-import:LED5MM")
      (libsource (lib "eagle-import") (part "LED5MM"))
    )
    (comp (ref "LED216")
      (value "LED5MM")
      (footprint "eagle-import:LED5MM")
      (libsource (lib "eagle-import") (part "LED5MM"))
    )
    (comp (ref "LED217")
      (value "LED5MM")
      (footprint "eagle-import:LED5MM")
      (libsource (lib "eagle-import") (part "LED5MM"))
    )
    (comp (ref "LED218")
      (value "LED5MM")
      (footprint "eagle-import:LED5MM")
      (libsource (lib "eagle-import") (part "LED5MM"))
    )
    (comp (ref "LED219")
      (value "LED5MM")
      (footprint "eagle-import:LED5MM")
      (libsource (lib "eagle-import") (part "LED5MM"))
    )
    (comp (ref "LED220")
      (value "LED5MM")
      (footprint "eagle-import:LED5MM")
      (libsource (lib "eagle-import") (part "LED5MM"))
    )
    (comp (ref "LED221")
      (value "LED5MM")
      (footprint "eagle-import:LED5MM")
      (libsource (lib "eagle-import") (part "LED5MM"))
    )
    (comp (ref "LED222")
      (value "LED5MM")
      (footprint "eagle-import:LED5MM")
      (libsource (lib "eagle-import") (part "LED5MM"))
    )
    (comp (ref "LED223")
      (value "LED5MM")
      (footprint "eagle-import:LED5MM")
      (libsource (lib "eagle-import") (part "LED5MM"))
    )
    (comp (ref "LED224")
      (value "LED5MM")
      (footprint "eagle-import:LED5MM")
      (libsource (lib "eagle-import") (part "LED5MM"))
    )
    (comp (ref "LED225")
      (value "LED5MM")
      (footprint "eagle-import:LED5MM")
      (libsource (lib "eagle-import") (part "LED5MM"))
    )
    (comp (ref "LED226")
      (value "LED5MM")
      (footprint "eagle-import:LED5MM")
      (libsource (lib "eagle-import") (part "LED5MM"))
    )
    (comp (ref "LED227")
      (value "LED5MM")
      (footprint "eagle-import:LED5MM")
      (libsource (lib "eagle-import") (part "LED5MM"))
    )
    (comp (ref "LED228")
      (value "LED5MM")
      (footprint "eagle-import:LED5MM")
      (libsource (lib "eagle-import") (part "LED5MM"))
    )
    (comp (ref "LED229")
      (value "LED5MM")
      (footprint "eagle-import:LED5MM")
      (libsource (lib "eagle-import") (part "LED5MM"))
    )
    (comp (ref "LED230")
      (value "LED5MM")
      (footprint "eagle-import:LED5MM")
      (libsource (lib "eagle-import") (part "LED5MM"))
    )
    (comp (ref "LED231")
      (value "LED5MM")
      (footprint "eagle-import:LED5MM")
      (libsource (lib "eagle-import") (part "LED5MM"))
    )
    (comp (ref "LED232")
      (value "LED5MM")
      (footprint "eagle-import:LED5MM")
      (libsource (lib "eagle-import") (part "LED5MM"))
    )
    (comp (ref "LED233")
      (value "LED5MM")
      (footprint "eagle-import:LED5MM")
      (libsource (lib "eagle-import") (part "LED5MM"))
    )
    (comp (ref "LED234")
      (value "LED5MM")
      (footprint "eagle-import:LED5MM")
      (libsource (lib "eagle-import") (part "LED5MM"))
    )
    (comp (ref "LED235")
      (value "LED5MM")
      (footprint "eagle-import:LED5MM")
      (libsource (lib "eagle-import") (part "LED5MM"))
    )
    (comp (ref "LED236")
      (value "LED5MM")
      (footprint "eagle-import:LED5MM")
      (libsource (lib "eagle-import") (part "LED5MM"))
    )
    (comp (ref "LED237")
      (value "LED5MM")
      (footprint "eagle-import:LED5MM")
      (libsource (lib "eagle-import") (part "LED5MM"))
    )
    (comp (ref "LED238")
      (value "LED5MM")
      (footprint "eagle-import:LED5MM")
      (libsource (lib "eagle-import") (part "LED5MM"))
    )
    (comp (ref "LED239")
      (value "LED5MM")
      (footprint "eagle-import:LED5MM")
      (libsource (lib "eagle-import") (part "LED5MM"))
    )
    (comp (ref "LED240")
      (value "LED5MM")
      (footprint "eagle-import:LED5MM")
      (libsource (lib "eagle-import") (part "LED5MM"))
    )
    (comp (ref "LED241")
      (value "LED5MM")
      (footprint "eagle-import:LED5MM")
      (libsource (lib "eagle-import") (part "LED5MM"))
    )
    (comp (ref "LED242")
      (value "LED5MM")
      (footprint "eagle-import:LED5MM")
      (libsource (lib "eagle-import") (part "LED5MM"))
    )
    (comp (ref "LED243")
      (value "LED5MM")
      (footprint "eagle-import:LED5MM")
      (libsource (lib "eagle-import") (part "LED5MM"))
    )
    (comp (ref "LED244")
      (value "LED5MM")
      (footprint "eagle-import:LED5MM")
      (libsource (lib "eagle-import") (part "LED5MM"))
    )
    (comp (ref "LED245")
      (value "LED5MM")
      (footprint "eagle-import:LED5MM")
      (libsource (lib "eagle-import") (part "LED5MM"))
    )
    (comp (ref "LED246")
      (value "LED5MM")
      (footprint "eagle-import:LED5MM")
      (libsource (lib "eagle-import") (part "LED5MM"))
    )
    (comp (ref "LED247")
      (value "LED5MM")
      (footprint "eagle-import:LED5MM")
      (libsource (lib "eagle-import") (part "LED5MM"))
    )
    (comp (ref "LED248")
      (value "LED5MM")
      (footprint "eagle-import:LED5MM")
      (libsource (lib "eagle-import") (part "LED5MM"))
    )
    (comp (ref "LED249")
      (value "LED5MM")
      (footprint "eagle-import:LED5MM")
      (libsource (lib "eagle-import") (part "LED5MM"))
    )
    (comp (ref "LED250")
      (value "LED5MM")
      (footprint "eagle-import:LED5MM")
      (libsource (lib "eagle-import") (part "LED5MM"))
    )
    (comp (ref "LED251")
      (value "LED5MM")
      (footprint "eagle-import:LED5MM")
      (libsource (lib "eagle-import") (part "LED5MM"))
    )
    (comp (ref "LED252")
      (value "LED5MM")
      (footprint "eagle-import:LED5MM")
      (libsource (lib "eagle-import") (part "LED5MM"))
    )
    (comp (ref "LED253")
      (value "LED5MM")
      (footprint "eagle-import:LED5MM")
      (libsource (lib "eagle-import") (part "LED5MM"))
    )
    (comp (ref "LED254")
      (value "LED5MM")
      (footprint "eagle-import:LED5MM")
      (libsource (lib "eagle-import") (part "LED5MM"))
    )
    (comp (ref "LED255")
      (value "LED5MM")
      (footprint "eagle-import:LED5MM")
      (libsource (lib "eagle-import") (part "LED5MM"))
    )
    (comp (ref "LED256")
      (value "LED5MM")
      (footprint "eagle-import:LED5MM")
      (libsource (lib "eagle-import") (part "LED5MM"))
    )
    (comp (ref "LED257")
      (value "LED5MM")
      (footprint "eagle-import:LED5MM")
      (libsource (lib "eagle-import") (part "LED5MM"))
    )
    (comp (ref "LED258")
      (value "LED5MM")
      (footprint "eagle-import:LED5MM")
      (libsource (lib "eagle-import") (part "LED5MM"))
    )
    (comp (ref "LED259")
      (value "LED5MM")
      (footprint "eagle-import:LED5MM")
      (libsource (lib "eagle-import") (part "LED5MM"))
    )
    (comp (ref "LED260")
      (value "LED5MM")
      (footprint "eagle-import:LED5MM")
      (libsource (lib "eagle-import") (part "LED5MM"))
    )
    (comp (ref "LED261")
      (value "LED5MM")
      (footprint "eagle-import:LED5MM")
      (libsource (lib "eagle-import") (part "LED5MM"))
    )
    (comp (ref "LED262")
      (value "LED5MM")
      (footprint "eagle-import:LED5MM")
      (libsource (lib "eagle-import") (part "LED5MM"))
    )
    (comp (ref "LED263")
      (value "LED5MM")
      (footprint "eagle-import:LED5MM")
      (libsource (lib "eagle-import") (part "LED5MM"))
    )
    (comp (ref "LED264")
      (value "LED5MM")
      (footprint "eagle-import:LED5MM")
      (libsource (lib "eagle-import") (part "LED5MM"))
    )
    (comp (ref "LED265")
      (value "LED5MM")
      (footprint "eagle-import:LED5MM")
      (libsource (lib "eagle-import") (part "LED5MM"))
    )
    (comp (ref "LED266")
      (value "LED5MM")
      (footprint "eagle-import:LED5MM")
      (libsource (lib "eagle-import") (part "LED5MM"))
    )
    (comp (ref "LED267")
      (value "LED5MM")
      (footprint "eagle-import:LED5MM")
      (libsource (lib "eagle-import") (part "LED5MM"))
    )
    (comp (ref "LED268")
      (value "LED5MM")
      (footprint "eagle-import:LED5MM")
      (libsource (lib "eagle-import") (part "LED5MM"))
    )
    (comp (ref "LED269")
      (value "LED5MM")
      (footprint "eagle-import:LED5MM")
      (libsource (lib "eagle-import") (part "LED5MM"))
    )
    (comp (ref "LED270")
      (value "LED5MM")
      (footprint "eagle-import:LED5MM")
      (libsource (lib "eagle-import") (part "LED5MM"))
    )
    (comp (ref "LED271")
      (value "LED5MM")
      (footprint "eagle-import:LED5MM")
      (libsource (lib "eagle-import") (part "LED5MM"))
    )
    (comp (ref "LED272")
      (value "LED5MM")
      (footprint "eagle-import:LED5MM")
      (libsource (lib "eagle-import") (part "LED5MM"))
    )
    (comp (ref "LED273")
      (value "LED5MM")
      (footprint "eagle-import:LED5MM")
      (libsource (lib "eagle-import") (part "LED5MM"))
    )
    (comp (ref "LED274")
      (value "LED5MM")
      (footprint "eagle-import:LED5MM")
      (libsource (lib "eagle-import") (part "LED5MM"))
    )
    (comp (ref "LED275")
      (value "LED5MM")
      (footprint "eagle-import:LED5MM")
      (libsource (lib "eagle-import") (part "LED5MM"))
    )
    (comp (ref "LED276")
      (value "LED5MM")
      (footprint "eagle-import:LED5MM")
      (libsource (lib "eagle-import") (part "LED5MM"))
    )
    (comp (ref "LED277")
      (value "LED5MM")
      (footprint "eagle-import:LED5MM")
      (libsource (lib "eagle-import") (part "LED5MM"))
    )
    (comp (ref "LED278")
      (value "LED5MM")
      (footprint "eagle-import:LED5MM")
      (libsource (lib "eagle-import") (part "LED5MM"))
    )
    (comp (ref "LED279")
      (value "LED5MM")
      (footprint "eagle-import:LED5MM")
      (libsource (lib "eagle-import") (part "LED5MM"))
    )
    (comp (ref "LED280")
      (value "LED5MM")
      (footprint "eagle-import:LED5MM")
      (libsource (lib "eagle-import") (part "LED5MM"))
    )
    (comp (ref "LED281")
      (value "LED5MM")
      (footprint "eagle-import:LED5MM")
      (libsource (lib "eagle-import") (part "LED5MM"))
    )
    (comp (ref "LED282")
      (value "LED5MM")
      (footprint "eagle-import:LED5MM")
      (libsource (lib "eagle-import") (part "LED5MM"))
    )
    (comp (ref "LED283")
      (value "LED5MM")
      (footprint "eagle-import:LED5MM")
      (libsource (lib "eagle-import") (part "LED5MM"))
    )
    (comp (ref "LED284")
      (value "LED5MM")
      (footprint "eagle-import:LED5MM")
      (libsource (lib "eagle-import") (part "LED5MM"))
    )
    (comp (ref "LED285")
      (value "LED5MM")
      (footprint "eagle-import:LED5MM")
      (libsource (lib "eagle-import") (part "LED5MM"))
    )
    (comp (ref "LED286")
      (value "LED5MM")
      (footprint "eagle-import:LED5MM")
      (libsource (lib "eagle-import") (part "LED5MM"))
    )
    (comp (ref "LED287")
      (value "LED5MM")
      (footprint "eagle-import:LED5MM")
      (libsource (lib "eagle-import") (part "LED5MM"))
    )
    (comp (ref "LED288")
      (value "LED5MM")
      (footprint "eagle-import:LED5MM")
      (libsource (lib "eagle-import") (part "LED5MM"))
    )
    (comp (ref "LED289")
      (value "LED5MM")
      (footprint "eagle-import:LED5MM")
      (libsource (lib "eagle-import") (part "LED5MM"))
    )
    (comp (ref "LED290")
      (value "LED5MM")
      (footprint "eagle-import:LED5MM")
      (libsource (lib "eagle-import") (part "LED5MM"))
    )
    (comp (ref "LED291")
      (value "LED5MM")
      (footprint "eagle-import:LED5MM")
      (libsource (lib "eagle-import") (part "LED5MM"))
    )
    (comp (ref "LED292")
      (value "LED5MM")
      (footprint "eagle-import:LED5MM")
      (libsource (lib "eagle-import") (part "LED5MM"))
    )
    (comp (ref "LED293")
      (value "LED5MM")
      (footprint "eagle-import:LED5MM")
      (libsource (lib "eagle-import") (part "LED5MM"))
    )
    (comp (ref "LED294")
      (value "LED5MM")
      (footprint "eagle-import:LED5MM")
      (libsource (lib "eagle-import") (part "LED5MM"))
    )
    (comp (ref "LED295")
      (value "LED5MM")
      (footprint "eagle-import:LED5MM")
      (libsource (lib "eagle-import") (part "LED5MM"))
    )
    (comp (ref "LED296")
      (value "LED5MM")
      (footprint "eagle-import:LED5MM")
      (libsource (lib "eagle-import") (part "LED5MM"))
    )
    (comp (ref "LED297")
      (value "LED5MM")
      (footprint "eagle-import:LED5MM")
      (libsource (lib "eagle-import") (part "LED5MM"))
    )
    (comp (ref "LED298")
      (value "LED5MM")
      (footprint "eagle-import:LED5MM")
      (libsource (lib "eagle-import") (part "LED5MM"))
    )
    (comp (ref "LED299")
      (value "LED5MM")
      (footprint "eagle-import:LED5MM")
      (libsource (lib "eagle-import") (part "LED5MM"))
    )
    (comp (ref "LED300")
      (value "LED5MM")
      (footprint "eagle-import:LED5MM")
      (libsource (lib "eagle-import") (part "LED5MM"))
    )
    (comp (ref "LED301")
      (value "LED5MM")
      (footprint "eagle-import:LED5MM")
      (libsource (lib "eagle-import") (part "LED5MM"))
    )
    (comp (ref "LED302")
      (value "LED5MM")
      (footprint "eagle-import:LED5MM")
      (libsource (lib "eagle-import") (part "LED5MM"))
    )
    (comp (ref "LED303")
      (value "LED5MM")
      (footprint "eagle-import:LED5MM")
      (libsource (lib "eagle-import") (part "LED5MM"))
    )
    (comp (ref "LED304")
      (value "LED5MM")
      (footprint "eagle-import:LED5MM")
      (libsource (lib "eagle-import") (part "LED5MM"))
    )
    (comp (ref "LED305")
      (value "LED5MM")
      (footprint "eagle-import:LED5MM")
      (libsource (lib "eagle-import") (part "LED5MM"))
    )
    (comp (ref "LED306")
      (value "LED5MM")
      (footprint "eagle-import:LED5MM")
      (libsource (lib "eagle-import") (part "LED5MM"))
    )
    (comp (ref "LED307")
      (value "LED5MM")
      (footprint "eagle-import:LED5MM")
      (libsource (lib "eagle-import") (part "LED5MM"))
    )
    (comp (ref "LED308")
      (value "LED5MM")
      (footprint "eagle-import:LED5MM")
      (libsource (lib "eagle-import") (part "LED5MM"))
    )
    (comp (ref "LED309")
      (value "LED5MM")
      (footprint "eagle-import:LED5MM")
      (libsource (lib "eagle-import") (part "LED5MM"))
    )
    (comp (ref "LED310")
      (value "LED5MM")
      (footprint "eagle-import:LED5MM")
      (libsource (lib "eagle-import") (part "LED5MM"))
    )
    (comp (ref "LED311")
      (value "LED5MM")
      (footprint "eagle-import:LED5MM")
      (libsource (lib "eagle-import") (part "LED5MM"))
    )
    (comp (ref "LED312")
      (value "LED5MM")
      (footprint "eagle-import:LED5MM")
      (libsource (lib "eagle-import") (part "LED5MM"))
    )
    (comp (ref "LED313")
      (value "LED5MM")
      (footprint "eagle-import:LED5MM")
      (libsource (lib "eagle-import") (part "LED5MM"))
    )
    (comp (ref "LED314")
      (value "LED5MM")
      (footprint "eagle-import:LED5MM")
      (libsource (lib "eagle-import") (part "LED5MM"))
    )
    (comp (ref "LED315")
      (value "LED5MM")
      (footprint "eagle-import:LED5MM")
      (libsource (lib "eagle-import") (part "LED5MM"))
    )
    (comp (ref "LED316")
      (value "LED5MM")
      (footprint "eagle-import:LED5MM")
      (libsource (lib "eagle-import") (part "LED5MM"))
    )
    (comp (ref "LED317")
      (value "LED5MM")
      (footprint "eagle-import:LED5MM")
      (libsource (lib "eagle-import") (part "LED5MM"))
    )
    (comp (ref "LED318")
      (value "LED5MM")
      (footprint "eagle-import:LED5MM")
      (libsource (lib "eagle-import") (part "LED5MM"))
    )
    (comp (ref "LED319")
      (value "LED5MM")
      (footprint "eagle-import:LED5MM")
      (libsource (lib "eagle-import") (part "LED5MM"))
    )
    (comp (ref "LED320")
      (value "LED5MM")
      (footprint "eagle-import:LED5MM")
      (libsource (lib "eagle-import") (part "LED5MM"))
    )
    (comp (ref "LED321")
      (value "LED5MM")
      (footprint "eagle-import:LED5MM")
      (libsource (lib "eagle-import") (part "LED5MM"))
    )
    (comp (ref "LED322")
      (value "LED5MM")
      (footprint "eagle-import:LED5MM")
      (libsource (lib "eagle-import") (part "LED5MM"))
    )
    (comp (ref "LED323")
      (value "LED5MM")
      (footprint "eagle-import:LED5MM")
      (libsource (lib "eagle-import") (part "LED5MM"))
    )
    (comp (ref "LED324")
      (value "LED5MM")
      (footprint "eagle-import:LED5MM")
      (libsource (lib "eagle-import") (part "LED5MM"))
    )
    (comp (ref "LED325")
      (value "LED5MM")
      (footprint "eagle-import:LED5MM")
      (libsource (lib "eagle-import") (part "LED5MM"))
    )
    (comp (ref "LED326")
      (value "LED5MM")
      (footprint "eagle-import:LED5MM")
      (libsource (lib "eagle-import") (part "LED5MM"))
    )
    (comp (ref "LED327")
      (value "LED5MM")
      (footprint "eagle-import:LED5MM")
      (libsource (lib "eagle-import") (part "LED5MM"))
    )
    (comp (ref "LED328")
      (value "LED5MM")
      (footprint "eagle-import:LED5MM")
      (libsource (lib "eagle-import") (part "LED5MM"))
    )
    (comp (ref "LED329")
      (value "LED5MM")
      (footprint "eagle-import:LED5MM")
      (libsource (lib "eagle-import") (part "LED5MM"))
    )
    (comp (ref "LED330")
      (value "LED5MM")
      (footprint "eagle-import:LED5MM")
      (libsource (lib "eagle-import") (part "LED5MM"))
    )
    (comp (ref "LED331")
      (value "LED5MM")
      (footprint "eagle-import:LED5MM")
      (libsource (lib "eagle-import") (part "LED5MM"))
    )
    (comp (ref "LED332")
      (value "LED5MM")
      (footprint "eagle-import:LED5MM")
      (libsource (lib "eagle-import") (part "LED5MM"))
    )
    (comp (ref "VCC")
      (value "3,17/1,3")
      (footprint "eagle-import:3,17_1,3")
      (libsource (lib "eagle-import") (part "3,17/1,3"))
    )
  )
  (nets
    (net (code "1") (name "GND") (class "Default")
      (node (ref "GND") (pin "1") (pinfunction "P_1") (pintype "passive"))
      (node (ref "LED1") (pin "K") (pinfunction "C_K") (pintype "passive"))
      (node (ref "LED118") (pin "K") (pinfunction "C_K") (pintype "passive"))
      (node (ref "LED138") (pin "K") (pinfunction "C_K") (pintype "passive"))
      (node (ref "LED157") (pin "K") (pinfunction "C_K") (pintype "passive"))
      (node (ref "LED177") (pin "K") (pinfunction "C_K") (pintype "passive"))
      (node (ref "LED196") (pin "K") (pinfunction "C_K") (pintype "passive"))
      (node (ref "LED21") (pin "K") (pinfunction "C_K") (pintype "passive"))
      (node (ref "LED216") (pin "K") (pinfunction "C_K") (pintype "passive"))
      (node (ref "LED235") (pin "K") (pinfunction "C_K") (pintype "passive"))
      (node (ref "LED255") (pin "K") (pinfunction "C_K") (pintype "passive"))
      (node (ref "LED274") (pin "K") (pinfunction "C_K") (pintype "passive"))
      (node (ref "LED294") (pin "K") (pinfunction "C_K") (pintype "passive"))
      (node (ref "LED313") (pin "K") (pinfunction "C_K") (pintype "passive"))
      (node (ref "LED40") (pin "K") (pinfunction "C_K") (pintype "passive"))
      (node (ref "LED60") (pin "K") (pinfunction "C_K") (pintype "passive"))
      (node (ref "LED79") (pin "K") (pinfunction "C_K") (pintype "passive"))
      (node (ref "LED99") (pin "K") (pinfunction "C_K") (pintype "passive"))
    )
    (net (code "2") (name "Net-(D1-PadC)") (class "Default")
      (node (ref "D1") (pin "C") (pinfunction "C_C") (pintype "passive"))
      (node (ref "LED20") (pin "A") (pinfunction "A_A") (pintype "passive"))
    )
    (net (code "3") (name "Net-(D2-PadC)") (class "Default")
      (node (ref "D2") (pin "C") (pinfunction "C_C") (pintype "passive"))
      (node (ref "LED39") (pin "A") (pinfunction "A_A") (pintype "passive"))
    )
    (net (code "4") (name "Net-(D3-PadC)") (class "Default")
      (node (ref "D3") (pin "C") (pinfunction "C_C") (pintype "passive"))
      (node (ref "LED59") (pin "A") (pinfunction "A_A") (pintype "passive"))
    )
    (net (code "5") (name "Net-(D4-PadC)") (class "Default")
      (node (ref "D4") (pin "C") (pinfunction "C_C") (pintype "passive"))
      (node (ref "LED78") (pin "A") (pinfunction "A_A") (pintype "passive"))
    )
    (net (code "6") (name "Net-(D5-PadC)") (class "Default")
      (node (ref "D5") (pin "C") (pinfunction "C_C") (pintype "passive"))
      (node (ref "LED98") (pin "A") (pinfunction "A_A") (pintype "passive"))
    )
    (net (code "7") (name "Net-(D6-PadC)") (class "Default")
      (node (ref "D6") (pin "C") (pinfunction "C_C") (pintype "passive"))
      (node (ref "LED117") (pin "A") (pinfunction "A_A") (pintype "passive"))
    )
    (net (code "8") (name "Net-(D7-PadC)") (class "Default")
      (node (ref "D7") (pin "C") (pinfunction "C_C") (pintype "passive"))
      (node (ref "LED137") (pin "A") (pinfunction "A_A") (pintype "passive"))
    )
    (net (code "9") (name "Net-(D8-PadC)") (class "Default")
      (node (ref "D8") (pin "C") (pinfunction "C_C") (pintype "passive"))
      (node (ref "LED156") (pin "A") (pinfunction "A_A") (pintype "passive"))
    )
    (net (code "10") (name "Net-(D9-PadC)") (class "Default")
      (node (ref "D9") (pin "C") (pinfunction "C_C") (pintype "passive"))
      (node (ref "LED176") (pin "A") (pinfunction "A_A") (pintype "passive"))
    )
    (net (code "11") (name "Net-(D10-PadC)") (class "Default")
      (node (ref "D10") (pin "C") (pinfunction "C_C") (pintype "passive"))
      (node (ref "LED195") (pin "A") (pinfunction "A_A") (pintype "passive"))
    )
    (net (code "12") (name "Net-(D11-PadC)") (class "Default")
      (node (ref "D11") (pin "C") (pinfunction "C_C") (pintype "passive"))
      (node (ref "LED215") (pin "A") (pinfunction "A_A") (pintype "passive"))
    )
    (net (code "13") (name "Net-(D12-PadC)") (class "Default")
      (node (ref "D12") (pin "C") (pinfunction "C_C") (pintype "passive"))
      (node (ref "LED234") (pin "A") (pinfunction "A_A") (pintype "passive"))
    )
    (net (code "14") (name "Net-(D13-PadC)") (class "Default")
      (node (ref "D13") (pin "C") (pinfunction "C_C") (pintype "passive"))
      (node (ref "LED254") (pin "A") (pinfunction "A_A") (pintype "passive"))
    )
    (net (code "15") (name "Net-(D14-PadC)") (class "Default")
      (node (ref "D14") (pin "C") (pinfunction "C_C") (pintype "passive"))
      (node (ref "LED273") (pin "A") (pinfunction "A_A") (pintype "passive"))
    )
    (net (code "16") (name "Net-(D15-PadC)") (class "Default")
      (node (ref "D15") (pin "C") (pinfunction "C_C") (pintype "passive"))
      (node (ref "LED293") (pin "A") (pinfunction "A_A") (pintype "passive"))
    )
    (net (code "17") (name "Net-(D16-PadC)") (class "Default")
      (node (ref "D16") (pin "C") (pinfunction "C_C") (pintype "passive"))
      (node (ref "LED312") (pin "A") (pinfunction "A_A") (pintype "passive"))
    )
    (net (code "18") (name "Net-(D17-PadC)") (class "Default")
      (node (ref "D17") (pin "C") (pinfunction "C_C") (pintype "passive"))
      (node (ref "LED332") (pin "A") (pinfunction "A_A") (pintype "passive"))
    )
    (net (code "19") (name "Net-(LED2-C)") (class "Default")
      (node (ref "LED1") (pin "A") (pinfunction "A_A") (pintype "passive"))
      (node (ref "LED2") (pin "K") (pinfunction "C_K") (pintype "passive"))
    )
    (net (code "20") (name "Net-(LED3-C)") (class "Default")
      (node (ref "LED2") (pin "A") (pinfunction "A_A") (pintype "passive"))
      (node (ref "LED3") (pin "K") (pinfunction "C_K") (pintype "passive"))
    )
    (net (code "21") (name "Net-(LED4-C)") (class "Default")
      (node (ref "LED3") (pin "A") (pinfunction "A_A") (pintype "passive"))
      (node (ref "LED4") (pin "K") (pinfunction "C_K") (pintype "passive"))
    )
    (net (code "22") (name "Net-(LED5-C)") (class "Default")
      (node (ref "LED4") (pin "A") (pinfunction "A_A") (pintype "passive"))
      (node (ref "LED5") (pin "K") (pinfunction "C_K") (pintype "passive"))
    )
    (net (code "23") (name "Net-(LED6-C)") (class "Default")
      (node (ref "LED5") (pin "A") (pinfunction "A_A") (pintype "passive"))
      (node (ref "LED6") (pin "K") (pinfunction "C_K") (pintype "passive"))
    )
    (net (code "24") (name "Net-(LED7-C)") (class "Default")
      (node (ref "LED6") (pin "A") (pinfunction "A_A") (pintype "passive"))
      (node (ref "LED7") (pin "K") (pinfunction "C_K") (pintype "passive"))
    )
    (net (code "25") (name "Net-(LED8-C)") (class "Default")
      (node (ref "LED7") (pin "A") (pinfunction "A_A") (pintype "passive"))
      (node (ref "LED8") (pin "K") (pinfunction "C_K") (pintype "passive"))
    )
    (net (code "26") (name "Net-(LED9-C)") (class "Default")
      (node (ref "LED8") (pin "A") (pinfunction "A_A") (pintype "passive"))
      (node (ref "LED9") (pin "K") (pinfunction "C_K") (pintype "passive"))
    )
    (net (code "27") (name "Net-(LED10-C)") (class "Default")
      (node (ref "LED10") (pin "K") (pinfunction "C_K") (pintype "passive"))
      (node (ref "LED9") (pin "A") (pinfunction "A_A") (pintype "passive"))
    )
    (net (code "28") (name "Net-(LED11-C)") (class "Default")
      (node (ref "LED10") (pin "A") (pinfunction "A_A") (pintype "passive"))
      (node (ref "LED11") (pin "K") (pinfunction "C_K") (pintype "passive"))
    )
    (net (code "29") (name "Net-(LED12-C)") (class "Default")
      (node (ref "LED11") (pin "A") (pinfunction "A_A") (pintype "passive"))
      (node (ref "LED12") (pin "K") (pinfunction "C_K") (pintype "passive"))
    )
    (net (code "30") (name "Net-(LED13-C)") (class "Default")
      (node (ref "LED12") (pin "A") (pinfunction "A_A") (pintype "passive"))
      (node (ref "LED13") (pin "K") (pinfunction "C_K") (pintype "passive"))
    )
    (net (code "31") (name "Net-(LED14-C)") (class "Default")
      (node (ref "LED13") (pin "A") (pinfunction "A_A") (pintype "passive"))
      (node (ref "LED14") (pin "K") (pinfunction "C_K") (pintype "passive"))
    )
    (net (code "32") (name "Net-(LED15-C)") (class "Default")
      (node (ref "LED14") (pin "A") (pinfunction "A_A") (pintype "passive"))
      (node (ref "LED15") (pin "K") (pinfunction "C_K") (pintype "passive"))
    )
    (net (code "33") (name "Net-(LED16-C)") (class "Default")
      (node (ref "LED15") (pin "A") (pinfunction "A_A") (pintype "passive"))
      (node (ref "LED16") (pin "K") (pinfunction "C_K") (pintype "passive"))
    )
    (net (code "34") (name "Net-(LED17-C)") (class "Default")
      (node (ref "LED16") (pin "A") (pinfunction "A_A") (pintype "passive"))
      (node (ref "LED17") (pin "K") (pinfunction "C_K") (pintype "passive"))
    )
    (net (code "35") (name "Net-(LED18-C)") (class "Default")
      (node (ref "LED17") (pin "A") (pinfunction "A_A") (pintype "passive"))
      (node (ref "LED18") (pin "K") (pinfunction "C_K") (pintype "passive"))
    )
    (net (code "36") (name "Net-(LED19-C)") (class "Default")
      (node (ref "LED18") (pin "A") (pinfunction "A_A") (pintype "passive"))
      (node (ref "LED19") (pin "K") (pinfunction "C_K") (pintype "passive"))
    )
    (net (code "37") (name "Net-(LED20-C)") (class "Default")
      (node (ref "LED19") (pin "A") (pinfunction "A_A") (pintype "passive"))
      (node (ref "LED20") (pin "K") (pinfunction "C_K") (pintype "passive"))
    )
    (net (code "38") (name "Net-(LED22-C)") (class "Default")
      (node (ref "LED21") (pin "A") (pinfunction "A_A") (pintype "passive"))
      (node (ref "LED22") (pin "K") (pinfunction "C_K") (pintype "passive"))
    )
    (net (code "39") (name "Net-(LED23-C)") (class "Default")
      (node (ref "LED22") (pin "A") (pinfunction "A_A") (pintype "passive"))
      (node (ref "LED23") (pin "K") (pinfunction "C_K") (pintype "passive"))
    )
    (net (code "40") (name "Net-(LED24-C)") (class "Default")
      (node (ref "LED23") (pin "A") (pinfunction "A_A") (pintype "passive"))
      (node (ref "LED24") (pin "K") (pinfunction "C_K") (pintype "passive"))
    )
    (net (code "41") (name "Net-(LED25-C)") (class "Default")
      (node (ref "LED24") (pin "A") (pinfunction "A_A") (pintype "passive"))
      (node (ref "LED25") (pin "K") (pinfunction "C_K") (pintype "passive"))
    )
    (net (code "42") (name "Net-(LED26-C)") (class "Default")
      (node (ref "LED25") (pin "A") (pinfunction "A_A") (pintype "passive"))
      (node (ref "LED26") (pin "K") (pinfunction "C_K") (pintype "passive"))
    )
    (net (code "43") (name "Net-(LED27-C)") (class "Default")
      (node (ref "LED26") (pin "A") (pinfunction "A_A") (pintype "passive"))
      (node (ref "LED27") (pin "K") (pinfunction "C_K") (pintype "passive"))
    )
    (net (code "44") (name "Net-(LED28-C)") (class "Default")
      (node (ref "LED27") (pin "A") (pinfunction "A_A") (pintype "passive"))
      (node (ref "LED28") (pin "K") (pinfunction "C_K") (pintype "passive"))
    )
    (net (code "45") (name "Net-(LED29-C)") (class "Default")
      (node (ref "LED28") (pin "A") (pinfunction "A_A") (pintype "passive"))
      (node (ref "LED29") (pin "K") (pinfunction "C_K") (pintype "passive"))
    )
    (net (code "46") (name "Net-(LED30-C)") (class "Default")
      (node (ref "LED29") (pin "A") (pinfunction "A_A") (pintype "passive"))
      (node (ref "LED30") (pin "K") (pinfunction "C_K") (pintype "passive"))
    )
    (net (code "47") (name "Net-(LED31-C)") (class "Default")
      (node (ref "LED30") (pin "A") (pinfunction "A_A") (pintype "passive"))
      (node (ref "LED31") (pin "K") (pinfunction "C_K") (pintype "passive"))
    )
    (net (code "48") (name "Net-(LED32-C)") (class "Default")
      (node (ref "LED31") (pin "A") (pinfunction "A_A") (pintype "passive"))
      (node (ref "LED32") (pin "K") (pinfunction "C_K") (pintype "passive"))
    )
    (net (code "49") (name "Net-(LED33-C)") (class "Default")
      (node (ref "LED32") (pin "A") (pinfunction "A_A") (pintype "passive"))
      (node (ref "LED33") (pin "K") (pinfunction "C_K") (pintype "passive"))
    )
    (net (code "50") (name "Net-(LED34-C)") (class "Default")
      (node (ref "LED33") (pin "A") (pinfunction "A_A") (pintype "passive"))
      (node (ref "LED34") (pin "K") (pinfunction "C_K") (pintype "passive"))
    )
    (net (code "51") (name "Net-(LED35-C)") (class "Default")
      (node (ref "LED34") (pin "A") (pinfunction "A_A") (pintype "passive"))
      (node (ref "LED35") (pin "K") (pinfunction "C_K") (pintype "passive"))
    )
    (net (code "52") (name "Net-(LED36-C)") (class "Default")
      (node (ref "LED35") (pin "A") (pinfunction "A_A") (pintype "passive"))
      (node (ref "LED36") (pin "K") (pinfunction "C_K") (pintype "passive"))
    )
    (net (code "53") (name "Net-(LED37-C)") (class "Default")
      (node (ref "LED36") (pin "A") (pinfunction "A_A") (pintype "passive"))
      (node (ref "LED37") (pin "K") (pinfunction "C_K") (pintype "passive"))
    )
    (net (code "54") (name "Net-(LED38-C)") (class "Default")
      (node (ref "LED37") (pin "A") (pinfunction "A_A") (pintype "passive"))
      (node (ref "LED38") (pin "K") (pinfunction "C_K") (pintype "passive"))
    )
    (net (code "55") (name "Net-(LED39-C)") (class "Default")
      (node (ref "LED38") (pin "A") (pinfunction "A_A") (pintype "passive"))
      (node (ref "LED39") (pin "K") (pinfunction "C_K") (pintype "passive"))
    )
    (net (code "56") (name "Net-(LED41-C)") (class "Default")
      (node (ref "LED40") (pin "A") (pinfunction "A_A") (pintype "passive"))
      (node (ref "LED41") (pin "K") (pinfunction "C_K") (pintype "passive"))
    )
    (net (code "57") (name "Net-(LED42-C)") (class "Default")
      (node (ref "LED41") (pin "A") (pinfunction "A_A") (pintype "passive"))
      (node (ref "LED42") (pin "K") (pinfunction "C_K") (pintype "passive"))
    )
    (net (code "58") (name "Net-(LED43-C)") (class "Default")
      (node (ref "LED42") (pin "A") (pinfunction "A_A") (pintype "passive"))
      (node (ref "LED43") (pin "K") (pinfunction "C_K") (pintype "passive"))
    )
    (net (code "59") (name "Net-(LED44-C)") (class "Default")
      (node (ref "LED43") (pin "A") (pinfunction "A_A") (pintype "passive"))
      (node (ref "LED44") (pin "K") (pinfunction "C_K") (pintype "passive"))
    )
    (net (code "60") (name "Net-(LED45-C)") (class "Default")
      (node (ref "LED44") (pin "A") (pinfunction "A_A") (pintype "passive"))
      (node (ref "LED45") (pin "K") (pinfunction "C_K") (pintype "passive"))
    )
    (net (code "61") (name "Net-(LED46-C)") (class "Default")
      (node (ref "LED45") (pin "A") (pinfunction "A_A") (pintype "passive"))
      (node (ref "LED46") (pin "K") (pinfunction "C_K") (pintype "passive"))
    )
    (net (code "62") (name "Net-(LED47-C)") (class "Default")
      (node (ref "LED46") (pin "A") (pinfunction "A_A") (pintype "passive"))
      (node (ref "LED47") (pin "K") (pinfunction "C_K") (pintype "passive"))
    )
    (net (code "63") (name "Net-(LED48-C)") (class "Default")
      (node (ref "LED47") (pin "A") (pinfunction "A_A") (pintype "passive"))
      (node (ref "LED48") (pin "K") (pinfunction "C_K") (pintype "passive"))
    )
    (net (code "64") (name "Net-(LED49-C)") (class "Default")
      (node (ref "LED48") (pin "A") (pinfunction "A_A") (pintype "passive"))
      (node (ref "LED49") (pin "K") (pinfunction "C_K") (pintype "passive"))
    )
    (net (code "65") (name "Net-(LED50-C)") (class "Default")
      (node (ref "LED49") (pin "A") (pinfunction "A_A") (pintype "passive"))
      (node (ref "LED50") (pin "K") (pinfunction "C_K") (pintype "passive"))
    )
    (net (code "66") (name "Net-(LED51-C)") (class "Default")
      (node (ref "LED50") (pin "A") (pinfunction "A_A") (pintype "passive"))
      (node (ref "LED51") (pin "K") (pinfunction "C_K") (pintype "passive"))
    )
    (net (code "67") (name "Net-(LED52-C)") (class "Default")
      (node (ref "LED51") (pin "A") (pinfunction "A_A") (pintype "passive"))
      (node (ref "LED52") (pin "K") (pinfunction "C_K") (pintype "passive"))
    )
    (net (code "68") (name "Net-(LED53-C)") (class "Default")
      (node (ref "LED52") (pin "A") (pinfunction "A_A") (pintype "passive"))
      (node (ref "LED53") (pin "K") (pinfunction "C_K") (pintype "passive"))
    )
    (net (code "69") (name "Net-(LED54-C)") (class "Default")
      (node (ref "LED53") (pin "A") (pinfunction "A_A") (pintype "passive"))
      (node (ref "LED54") (pin "K") (pinfunction "C_K") (pintype "passive"))
    )
    (net (code "70") (name "Net-(LED55-C)") (class "Default")
      (node (ref "LED54") (pin "A") (pinfunction "A_A") (pintype "passive"))
      (node (ref "LED55") (pin "K") (pinfunction "C_K") (pintype "passive"))
    )
    (net (code "71") (name "Net-(LED56-C)") (class "Default")
      (node (ref "LED55") (pin "A") (pinfunction "A_A") (pintype "passive"))
      (node (ref "LED56") (pin "K") (pinfunction "C_K") (pintype "passive"))
    )
    (net (code "72") (name "Net-(LED57-C)") (class "Default")
      (node (ref "LED56") (pin "A") (pinfunction "A_A") (pintype "passive"))
      (node (ref "LED57") (pin "K") (pinfunction "C_K") (pintype "passive"))
    )
    (net (code "73") (name "Net-(LED58-C)") (class "Default")
      (node (ref "LED57") (pin "A") (pinfunction "A_A") (pintype "passive"))
      (node (ref "LED58") (pin "K") (pinfunction "C_K") (pintype "passive"))
    )
    (net (code "74") (name "Net-(LED59-C)") (class "Default")
      (node (ref "LED58") (pin "A") (pinfunction "A_A") (pintype "passive"))
      (node (ref "LED59") (pin "K") (pinfunction "C_K") (pintype "passive"))
    )
    (net (code "75") (name "Net-(LED61-C)") (class "Default")
      (node (ref "LED60") (pin "A") (pinfunction "A_A") (pintype "passive"))
      (node (ref "LED61") (pin "K") (pinfunction "C_K") (pintype "passive"))
    )
    (net (code "76") (name "Net-(LED62-C)") (class "Default")
      (node (ref "LED61") (pin "A") (pinfunction "A_A") (pintype "passive"))
      (node (ref "LED62") (pin "K") (pinfunction "C_K") (pintype "passive"))
    )
    (net (code "77") (name "Net-(LED63-C)") (class "Default")
      (node (ref "LED62") (pin "A") (pinfunction "A_A") (pintype "passive"))
      (node (ref "LED63") (pin "K") (pinfunction "C_K") (pintype "passive"))
    )
    (net (code "78") (name "Net-(LED64-C)") (class "Default")
      (node (ref "LED63") (pin "A") (pinfunction "A_A") (pintype "passive"))
      (node (ref "LED64") (pin "K") (pinfunction "C_K") (pintype "passive"))
    )
    (net (code "79") (name "Net-(LED65-C)") (class "Default")
      (node (ref "LED64") (pin "A") (pinfunction "A_A") (pintype "passive"))
      (node (ref "LED65") (pin "K") (pinfunction "C_K") (pintype "passive"))
    )
    (net (code "80") (name "Net-(LED66-C)") (class "Default")
      (node (ref "LED65") (pin "A") (pinfunction "A_A") (pintype "passive"))
      (node (ref "LED66") (pin "K") (pinfunction "C_K") (pintype "passive"))
    )
    (net (code "81") (name "Net-(LED67-C)") (class "Default")
      (node (ref "LED66") (pin "A") (pinfunction "A_A") (pintype "passive"))
      (node (ref "LED67") (pin "K") (pinfunction "C_K") (pintype "passive"))
    )
    (net (code "82") (name "Net-(LED68-C)") (class "Default")
      (node (ref "LED67") (pin "A") (pinfunction "A_A") (pintype "passive"))
      (node (ref "LED68") (pin "K") (pinfunction "C_K") (pintype "passive"))
    )
    (net (code "83") (name "Net-(LED69-C)") (class "Default")
      (node (ref "LED68") (pin "A") (pinfunction "A_A") (pintype "passive"))
      (node (ref "LED69") (pin "K") (pinfunction "C_K") (pintype "passive"))
    )
    (net (code "84") (name "Net-(LED70-C)") (class "Default")
      (node (ref "LED69") (pin "A") (pinfunction "A_A") (pintype "passive"))
      (node (ref "LED70") (pin "K") (pinfunction "C_K") (pintype "passive"))
    )
    (net (code "85") (name "Net-(LED71-C)") (class "Default")
      (node (ref "LED70") (pin "A") (pinfunction "A_A") (pintype "passive"))
      (node (ref "LED71") (pin "K") (pinfunction "C_K") (pintype "passive"))
    )
    (net (code "86") (name "Net-(LED72-C)") (class "Default")
      (node (ref "LED71") (pin "A") (pinfunction "A_A") (pintype "passive"))
      (node (ref "LED72") (pin "K") (pinfunction "C_K") (pintype "passive"))
    )
    (net (code "87") (name "Net-(LED73-C)") (class "Default")
      (node (ref "LED72") (pin "A") (pinfunction "A_A") (pintype "passive"))
      (node (ref "LED73") (pin "K") (pinfunction "C_K") (pintype "passive"))
    )
    (net (code "88") (name "Net-(LED74-C)") (class "Default")
      (node (ref "LED73") (pin "A") (pinfunction "A_A") (pintype "passive"))
      (node (ref "LED74") (pin "K") (pinfunction "C_K") (pintype "passive"))
    )
    (net (code "89") (name "Net-(LED75-C)") (class "Default")
      (node (ref "LED74") (pin "A") (pinfunction "A_A") (pintype "passive"))
      (node (ref "LED75") (pin "K") (pinfunction "C_K") (pintype "passive"))
    )
    (net (code "90") (name "Net-(LED76-C)") (class "Default")
      (node (ref "LED75") (pin "A") (pinfunction "A_A") (pintype "passive"))
      (node (ref "LED76") (pin "K") (pinfunction "C_K") (pintype "passive"))
    )
    (net (code "91") (name "Net-(LED77-C)") (class "Default")
      (node (ref "LED76") (pin "A") (pinfunction "A_A") (pintype "passive"))
      (node (ref "LED77") (pin "K") (pinfunction "C_K") (pintype "passive"))
    )
    (net (code "92") (name "Net-(LED78-C)") (class "Default")
      (node (ref "LED77") (pin "A") (pinfunction "A_A") (pintype "passive"))
      (node (ref "LED78") (pin "K") (pinfunction "C_K") (pintype "passive"))
    )
    (net (code "93") (name "Net-(LED80-C)") (class "Default")
      (node (ref "LED79") (pin "A") (pinfunction "A_A") (pintype "passive"))
      (node (ref "LED80") (pin "K") (pinfunction "C_K") (pintype "passive"))
    )
    (net (code "94") (name "Net-(LED81-C)") (class "Default")
      (node (ref "LED80") (pin "A") (pinfunction "A_A") (pintype "passive"))
      (node (ref "LED81") (pin "K") (pinfunction "C_K") (pintype "passive"))
    )
    (net (code "95") (name "Net-(LED82-C)") (class "Default")
      (node (ref "LED81") (pin "A") (pinfunction "A_A") (pintype "passive"))
      (node (ref "LED82") (pin "K") (pinfunction "C_K") (pintype "passive"))
    )
    (net (code "96") (name "Net-(LED83-C)") (class "Default")
      (node (ref "LED82") (pin "A") (pinfunction "A_A") (pintype "passive"))
      (node (ref "LED83") (pin "K") (pinfunction "C_K") (pintype "passive"))
    )
    (net (code "97") (name "Net-(LED84-C)") (class "Default")
      (node (ref "LED83") (pin "A") (pinfunction "A_A") (pintype "passive"))
      (node (ref "LED84") (pin "K") (pinfunction "C_K") (pintype "passive"))
    )
    (net (code "98") (name "Net-(LED85-C)") (class "Default")
      (node (ref "LED84") (pin "A") (pinfunction "A_A") (pintype "passive"))
      (node (ref "LED85") (pin "K") (pinfunction "C_K") (pintype "passive"))
    )
    (net (code "99") (name "Net-(LED86-C)") (class "Default")
      (node (ref "LED85") (pin "A") (pinfunction "A_A") (pintype "passive"))
      (node (ref "LED86") (pin "K") (pinfunction "C_K") (pintype "passive"))
    )
    (net (code "100") (name "Net-(LED87-C)") (class "Default")
      (node (ref "LED86") (pin "A") (pinfunction "A_A") (pintype "passive"))
      (node (ref "LED87") (pin "K") (pinfunction "C_K") (pintype "passive"))
    )
    (net (code "101") (name "Net-(LED88-C)") (class "Default")
      (node (ref "LED87") (pin "A") (pinfunction "A_A") (pintype "passive"))
      (node (ref "LED88") (pin "K") (pinfunction "C_K") (pintype "passive"))
    )
    (net (code "102") (name "Net-(LED89-C)") (class "Default")
      (node (ref "LED88") (pin "A") (pinfunction "A_A") (pintype "passive"))
      (node (ref "LED89") (pin "K") (pinfunction "C_K") (pintype "passive"))
    )
    (net (code "103") (name "Net-(LED90-C)") (class "Default")
      (node (ref "LED89") (pin "A") (pinfunction "A_A") (pintype "passive"))
      (node (ref "LED90") (pin "K") (pinfunction "C_K") (pintype "passive"))
    )
    (net (code "104") (name "Net-(LED91-C)") (class "Default")
      (node (ref "LED90") (pin "A") (pinfunction "A_A") (pintype "passive"))
      (node (ref "LED91") (pin "K") (pinfunction "C_K") (pintype "passive"))
    )
    (net (code "105") (name "Net-(LED92-C)") (class "Default")
      (node (ref "LED91") (pin "A") (pinfunction "A_A") (pintype "passive"))
      (node (ref "LED92") (pin "K") (pinfunction "C_K") (pintype "passive"))
    )
    (net (code "106") (name "Net-(LED93-C)") (class "Default")
      (node (ref "LED92") (pin "A") (pinfunction "A_A") (pintype "passive"))
      (node (ref "LED93") (pin "K") (pinfunction "C_K") (pintype "passive"))
    )
    (net (code "107") (name "Net-(LED94-C)") (class "Default")
      (node (ref "LED93") (pin "A") (pinfunction "A_A") (pintype "passive"))
      (node (ref "LED94") (pin "K") (pinfunction "C_K") (pintype "passive"))
    )
    (net (code "108") (name "Net-(LED95-C)") (class "Default")
      (node (ref "LED94") (pin "A") (pinfunction "A_A") (pintype "passive"))
      (node (ref "LED95") (pin "K") (pinfunction "C_K") (pintype "passive"))
    )
    (net (code "109") (name "Net-(LED96-C)") (class "Default")
      (node (ref "LED95") (pin "A") (pinfunction "A_A") (pintype "passive"))
      (node (ref "LED96") (pin "K") (pinfunction "C_K") (pintype "passive"))
    )
    (net (code "110") (name "Net-(LED97-C)") (class "Default")
      (node (ref "LED96") (pin "A") (pinfunction "A_A") (pintype "passive"))
      (node (ref "LED97") (pin "K") (pinfunction "C_K") (pintype "passive"))
    )
    (net (code "111") (name "Net-(LED98-C)") (class "Default")
      (node (ref "LED97") (pin "A") (pinfunction "A_A") (pintype "passive"))
      (node (ref "LED98") (pin "K") (pinfunction "C_K") (pintype "passive"))
    )
    (net (code "112") (name "Net-(LED100-C)") (class "Default")
      (node (ref "LED100") (pin "K") (pinfunction "C_K") (pintype "passive"))
      (node (ref "LED99") (pin "A") (pinfunction "A_A") (pintype "passive"))
    )
    (net (code "113") (name "Net-(LED101-C)") (class "Default")
      (node (ref "LED100") (pin "A") (pinfunction "A_A") (pintype "passive"))
      (node (ref "LED101") (pin "K") (pinfunction "C_K") (pintype "passive"))
    )
    (net (code "114") (name "Net-(LED102-C)") (class "Default")
      (node (ref "LED101") (pin "A") (pinfunction "A_A") (pintype "passive"))
      (node (ref "LED102") (pin "K") (pinfunction "C_K") (pintype "passive"))
    )
    (net (code "115") (name "Net-(LED103-C)") (class "Default")
      (node (ref "LED102") (pin "A") (pinfunction "A_A") (pintype "passive"))
      (node (ref "LED103") (pin "K") (pinfunction "C_K") (pintype "passive"))
    )
    (net (code "116") (name "Net-(LED104-C)") (class "Default")
      (node (ref "LED103") (pin "A") (pinfunction "A_A") (pintype "passive"))
      (node (ref "LED104") (pin "K") (pinfunction "C_K") (pintype "passive"))
    )
    (net (code "117") (name "Net-(LED105-C)") (class "Default")
      (node (ref "LED104") (pin "A") (pinfunction "A_A") (pintype "passive"))
      (node (ref "LED105") (pin "K") (pinfunction "C_K") (pintype "passive"))
    )
    (net (code "118") (name "Net-(LED106-C)") (class "Default")
      (node (ref "LED105") (pin "A") (pinfunction "A_A") (pintype "passive"))
      (node (ref "LED106") (pin "K") (pinfunction "C_K") (pintype "passive"))
    )
    (net (code "119") (name "Net-(LED107-C)") (class "Default")
      (node (ref "LED106") (pin "A") (pinfunction "A_A") (pintype "passive"))
      (node (ref "LED107") (pin "K") (pinfunction "C_K") (pintype "passive"))
    )
    (net (code "120") (name "Net-(LED108-C)") (class "Default")
      (node (ref "LED107") (pin "A") (pinfunction "A_A") (pintype "passive"))
      (node (ref "LED108") (pin "K") (pinfunction "C_K") (pintype "passive"))
    )
    (net (code "121") (name "Net-(LED109-C)") (class "Default")
      (node (ref "LED108") (pin "A") (pinfunction "A_A") (pintype "passive"))
      (node (ref "LED109") (pin "K") (pinfunction "C_K") (pintype "passive"))
    )
    (net (code "122") (name "Net-(LED110-C)") (class "Default")
      (node (ref "LED109") (pin "A") (pinfunction "A_A") (pintype "passive"))
      (node (ref "LED110") (pin "K") (pinfunction "C_K") (pintype "passive"))
    )
    (net (code "123") (name "Net-(LED111-C)") (class "Default")
      (node (ref "LED110") (pin "A") (pinfunction "A_A") (pintype "passive"))
      (node (ref "LED111") (pin "K") (pinfunction "C_K") (pintype "passive"))
    )
    (net (code "124") (name "Net-(LED112-C)") (class "Default")
      (node (ref "LED111") (pin "A") (pinfunction "A_A") (pintype "passive"))
      (node (ref "LED112") (pin "K") (pinfunction "C_K") (pintype "passive"))
    )
    (net (code "125") (name "Net-(LED113-C)") (class "Default")
      (node (ref "LED112") (pin "A") (pinfunction "A_A") (pintype "passive"))
      (node (ref "LED113") (pin "K") (pinfunction "C_K") (pintype "passive"))
    )
    (net (code "126") (name "Net-(LED114-C)") (class "Default")
      (node (ref "LED113") (pin "A") (pinfunction "A_A") (pintype "passive"))
      (node (ref "LED114") (pin "K") (pinfunction "C_K") (pintype "passive"))
    )
    (net (code "127") (name "Net-(LED115-C)") (class "Default")
      (node (ref "LED114") (pin "A") (pinfunction "A_A") (pintype "passive"))
      (node (ref "LED115") (pin "K") (pinfunction "C_K") (pintype "passive"))
    )
    (net (code "128") (name "Net-(LED116-C)") (class "Default")
      (node (ref "LED115") (pin "A") (pinfunction "A_A") (pintype "passive"))
      (node (ref "LED116") (pin "K") (pinfunction "C_K") (pintype "passive"))
    )
    (net (code "129") (name "Net-(LED117-C)") (class "Default")
      (node (ref "LED116") (pin "A") (pinfunction "A_A") (pintype "passive"))
      (node (ref "LED117") (pin "K") (pinfunction "C_K") (pintype "passive"))
    )
    (net (code "130") (name "Net-(LED119-C)") (class "Default")
      (node (ref "LED118") (pin "A") (pinfunction "A_A") (pintype "passive"))
      (node (ref "LED119") (pin "K") (pinfunction "C_K") (pintype "passive"))
    )
    (net (code "131") (name "Net-(LED120-C)") (class "Default")
      (node (ref "LED119") (pin "A") (pinfunction "A_A") (pintype "passive"))
      (node (ref "LED120") (pin "K") (pinfunction "C_K") (pintype "passive"))
    )
    (net (code "132") (name "Net-(LED121-C)") (class "Default")
      (node (ref "LED120") (pin "A") (pinfunction "A_A") (pintype "passive"))
      (node (ref "LED121") (pin "K") (pinfunction "C_K") (pintype "passive"))
    )
    (net (code "133") (name "Net-(LED122-C)") (class "Default")
      (node (ref "LED121") (pin "A") (pinfunction "A_A") (pintype "passive"))
      (node (ref "LED122") (pin "K") (pinfunction "C_K") (pintype "passive"))
    )
    (net (code "134") (name "Net-(LED123-C)") (class "Default")
      (node (ref "LED122") (pin "A") (pinfunction "A_A") (pintype "passive"))
      (node (ref "LED123") (pin "K") (pinfunction "C_K") (pintype "passive"))
    )
    (net (code "135") (name "Net-(LED124-C)") (class "Default")
      (node (ref "LED123") (pin "A") (pinfunction "A_A") (pintype "passive"))
      (node (ref "LED124") (pin "K") (pinfunction "C_K") (pintype "passive"))
    )
    (net (code "136") (name "Net-(LED125-C)") (class "Default")
      (node (ref "LED124") (pin "A") (pinfunction "A_A") (pintype "passive"))
      (node (ref "LED125") (pin "K") (pinfunction "C_K") (pintype "passive"))
    )
    (net (code "137") (name "Net-(LED126-C)") (class "Default")
      (node (ref "LED125") (pin "A") (pinfunction "A_A") (pintype "passive"))
      (node (ref "LED126") (pin "K") (pinfunction "C_K") (pintype "passive"))
    )
    (net (code "138") (name "Net-(LED127-C)") (class "Default")
      (node (ref "LED126") (pin "A") (pinfunction "A_A") (pintype "passive"))
      (node (ref "LED127") (pin "K") (pinfunction "C_K") (pintype "passive"))
    )
    (net (code "139") (name "Net-(LED128-C)") (class "Default")
      (node (ref "LED127") (pin "A") (pinfunction "A_A") (pintype "passive"))
      (node (ref "LED128") (pin "K") (pinfunction "C_K") (pintype "passive"))
    )
    (net (code "140") (name "Net-(LED129-C)") (class "Default")
      (node (ref "LED128") (pin "A") (pinfunction "A_A") (pintype "passive"))
      (node (ref "LED129") (pin "K") (pinfunction "C_K") (pintype "passive"))
    )
    (net (code "141") (name "Net-(LED130-C)") (class "Default")
      (node (ref "LED129") (pin "A") (pinfunction "A_A") (pintype "passive"))
      (node (ref "LED130") (pin "K") (pinfunction "C_K") (pintype "passive"))
    )
    (net (code "142") (name "Net-(LED131-C)") (class "Default")
      (node (ref "LED130") (pin "A") (pinfunction "A_A") (pintype "passive"))
      (node (ref "LED131") (pin "K") (pinfunction "C_K") (pintype "passive"))
    )
    (net (code "143") (name "Net-(LED132-C)") (class "Default")
      (node (ref "LED131") (pin "A") (pinfunction "A_A") (pintype "passive"))
      (node (ref "LED132") (pin "K") (pinfunction "C_K") (pintype "passive"))
    )
    (net (code "144") (name "Net-(LED133-C)") (class "Default")
      (node (ref "LED132") (pin "A") (pinfunction "A_A") (pintype "passive"))
      (node (ref "LED133") (pin "K") (pinfunction "C_K") (pintype "passive"))
    )
    (net (code "145") (name "Net-(LED134-C)") (class "Default")
      (node (ref "LED133") (pin "A") (pinfunction "A_A") (pintype "passive"))
      (node (ref "LED134") (pin "K") (pinfunction "C_K") (pintype "passive"))
    )
    (net (code "146") (name "Net-(LED135-C)") (class "Default")
      (node (ref "LED134") (pin "A") (pinfunction "A_A") (pintype "passive"))
      (node (ref "LED135") (pin "K") (pinfunction "C_K") (pintype "passive"))
    )
    (net (code "147") (name "Net-(LED136-C)") (class "Default")
      (node (ref "LED135") (pin "A") (pinfunction "A_A") (pintype "passive"))
      (node (ref "LED136") (pin "K") (pinfunction "C_K") (pintype "passive"))
    )
    (net (code "148") (name "Net-(LED137-C)") (class "Default")
      (node (ref "LED136") (pin "A") (pinfunction "A_A") (pintype "passive"))
      (node (ref "LED137") (pin "K") (pinfunction "C_K") (pintype "passive"))
    )
    (net (code "149") (name "Net-(LED139-C)") (class "Default")
      (node (ref "LED138") (pin "A") (pinfunction "A_A") (pintype "passive"))
      (node (ref "LED139") (pin "K") (pinfunction "C_K") (pintype "passive"))
    )
    (net (code "150") (name "Net-(LED140-C)") (class "Default")
      (node (ref "LED139") (pin "A") (pinfunction "A_A") (pintype "passive"))
      (node (ref "LED140") (pin "K") (pinfunction "C_K") (pintype "passive"))
    )
    (net (code "151") (name "Net-(LED141-C)") (class "Default")
      (node (ref "LED140") (pin "A") (pinfunction "A_A") (pintype "passive"))
      (node (ref "LED141") (pin "K") (pinfunction "C_K") (pintype "passive"))
    )
    (net (code "152") (name "Net-(LED142-C)") (class "Default")
      (node (ref "LED141") (pin "A") (pinfunction "A_A") (pintype "passive"))
      (node (ref "LED142") (pin "K") (pinfunction "C_K") (pintype "passive"))
    )
    (net (code "153") (name "Net-(LED143-C)") (class "Default")
      (node (ref "LED142") (pin "A") (pinfunction "A_A") (pintype "passive"))
      (node (ref "LED143") (pin "K") (pinfunction "C_K") (pintype "passive"))
    )
    (net (code "154") (name "Net-(LED144-C)") (class "Default")
      (node (ref "LED143") (pin "A") (pinfunction "A_A") (pintype "passive"))
      (node (ref "LED144") (pin "K") (pinfunction "C_K") (pintype "passive"))
    )
    (net (code "155") (name "Net-(LED145-C)") (class "Default")
      (node (ref "LED144") (pin "A") (pinfunction "A_A") (pintype "passive"))
      (node (ref "LED145") (pin "K") (pinfunction "C_K") (pintype "passive"))
    )
    (net (code "156") (name "Net-(LED146-C)") (class "Default")
      (node (ref "LED145") (pin "A") (pinfunction "A_A") (pintype "passive"))
      (node (ref "LED146") (pin "K") (pinfunction "C_K") (pintype "passive"))
    )
    (net (code "157") (name "Net-(LED147-C)") (class "Default")
      (node (ref "LED146") (pin "A") (pinfunction "A_A") (pintype "passive"))
      (node (ref "LED147") (pin "K") (pinfunction "C_K") (pintype "passive"))
    )
    (net (code "158") (name "Net-(LED148-C)") (class "Default")
      (node (ref "LED147") (pin "A") (pinfunction "A_A") (pintype "passive"))
      (node (ref "LED148") (pin "K") (pinfunction "C_K") (pintype "passive"))
    )
    (net (code "159") (name "Net-(LED149-C)") (class "Default")
      (node (ref "LED148") (pin "A") (pinfunction "A_A") (pintype "passive"))
      (node (ref "LED149") (pin "K") (pinfunction "C_K") (pintype "passive"))
    )
    (net (code "160") (name "Net-(LED150-C)") (class "Default")
      (node (ref "LED149") (pin "A") (pinfunction "A_A") (pintype "passive"))
      (node (ref "LED150") (pin "K") (pinfunction "C_K") (pintype "passive"))
    )
    (net (code "161") (name "Net-(LED151-C)") (class "Default")
      (node (ref "LED150") (pin "A") (pinfunction "A_A") (pintype "passive"))
      (node (ref "LED151") (pin "K") (pinfunction "C_K") (pintype "passive"))
    )
    (net (code "162") (name "Net-(LED152-C)") (class "Default")
      (node (ref "LED151") (pin "A") (pinfunction "A_A") (pintype "passive"))
      (node (ref "LED152") (pin "K") (pinfunction "C_K") (pintype "passive"))
    )
    (net (code "163") (name "Net-(LED153-C)") (class "Default")
      (node (ref "LED152") (pin "A") (pinfunction "A_A") (pintype "passive"))
      (node (ref "LED153") (pin "K") (pinfunction "C_K") (pintype "passive"))
    )
    (net (code "164") (name "Net-(LED154-C)") (class "Default")
      (node (ref "LED153") (pin "A") (pinfunction "A_A") (pintype "passive"))
      (node (ref "LED154") (pin "K") (pinfunction "C_K") (pintype "passive"))
    )
    (net (code "165") (name "Net-(LED155-C)") (class "Default")
      (node (ref "LED154") (pin "A") (pinfunction "A_A") (pintype "passive"))
      (node (ref "LED155") (pin "K") (pinfunction "C_K") (pintype "passive"))
    )
    (net (code "166") (name "Net-(LED156-C)") (class "Default")
      (node (ref "LED155") (pin "A") (pinfunction "A_A") (pintype "passive"))
      (node (ref "LED156") (pin "K") (pinfunction "C_K") (pintype "passive"))
    )
    (net (code "167") (name "Net-(LED158-C)") (class "Default")
      (node (ref "LED157") (pin "A") (pinfunction "A_A") (pintype "passive"))
      (node (ref "LED158") (pin "K") (pinfunction "C_K") (pintype "passive"))
    )
    (net (code "168") (name "Net-(LED159-C)") (class "Default")
      (node (ref "LED158") (pin "A") (pinfunction "A_A") (pintype "passive"))
      (node (ref "LED159") (pin "K") (pinfunction "C_K") (pintype "passive"))
    )
    (net (code "169") (name "Net-(LED160-C)") (class "Default")
      (node (ref "LED159") (pin "A") (pinfunction "A_A") (pintype "passive"))
      (node (ref "LED160") (pin "K") (pinfunction "C_K") (pintype "passive"))
    )
    (net (code "170") (name "Net-(LED161-C)") (class "Default")
      (node (ref "LED160") (pin "A") (pinfunction "A_A") (pintype "passive"))
      (node (ref "LED161") (pin "K") (pinfunction "C_K") (pintype "passive"))
    )
    (net (code "171") (name "Net-(LED162-C)") (class "Default")
      (node (ref "LED161") (pin "A") (pinfunction "A_A") (pintype "passive"))
      (node (ref "LED162") (pin "K") (pinfunction "C_K") (pintype "passive"))
    )
    (net (code "172") (name "Net-(LED163-C)") (class "Default")
      (node (ref "LED162") (pin "A") (pinfunction "A_A") (pintype "passive"))
      (node (ref "LED163") (pin "K") (pinfunction "C_K") (pintype "passive"))
    )
    (net (code "173") (name "Net-(LED164-C)") (class "Default")
      (node (ref "LED163") (pin "A") (pinfunction "A_A") (pintype "passive"))
      (node (ref "LED164") (pin "K") (pinfunction "C_K") (pintype "passive"))
    )
    (net (code "174") (name "Net-(LED165-C)") (class "Default")
      (node (ref "LED164") (pin "A") (pinfunction "A_A") (pintype "passive"))
      (node (ref "LED165") (pin "K") (pinfunction "C_K") (pintype "passive"))
    )
    (net (code "175") (name "Net-(LED166-C)") (class "Default")
      (node (ref "LED165") (pin "A") (pinfunction "A_A") (pintype "passive"))
      (node (ref "LED166") (pin "K") (pinfunction "C_K") (pintype "passive"))
    )
    (net (code "176") (name "Net-(LED167-C)") (class "Default")
      (node (ref "LED166") (pin "A") (pinfunction "A_A") (pintype "passive"))
      (node (ref "LED167") (pin "K") (pinfunction "C_K") (pintype "passive"))
    )
    (net (code "177") (name "Net-(LED168-C)") (class "Default")
      (node (ref "LED167") (pin "A") (pinfunction "A_A") (pintype "passive"))
      (node (ref "LED168") (pin "K") (pinfunction "C_K") (pintype "passive"))
    )
    (net (code "178") (name "Net-(LED169-C)") (class "Default")
      (node (ref "LED168") (pin "A") (pinfunction "A_A") (pintype "passive"))
      (node (ref "LED169") (pin "K") (pinfunction "C_K") (pintype "passive"))
    )
    (net (code "179") (name "Net-(LED170-C)") (class "Default")
      (node (ref "LED169") (pin "A") (pinfunction "A_A") (pintype "passive"))
      (node (ref "LED170") (pin "K") (pinfunction "C_K") (pintype "passive"))
    )
    (net (code "180") (name "Net-(LED171-C)") (class "Default")
      (node (ref "LED170") (pin "A") (pinfunction "A_A") (pintype "passive"))
      (node (ref "LED171") (pin "K") (pinfunction "C_K") (pintype "passive"))
    )
    (net (code "181") (name "Net-(LED172-C)") (class "Default")
      (node (ref "LED171") (pin "A") (pinfunction "A_A") (pintype "passive"))
      (node (ref "LED172") (pin "K") (pinfunction "C_K") (pintype "passive"))
    )
    (net (code "182") (name "Net-(LED173-C)") (class "Default")
      (node (ref "LED172") (pin "A") (pinfunction "A_A") (pintype "passive"))
      (node (ref "LED173") (pin "K") (pinfunction "C_K") (pintype "passive"))
    )
    (net (code "183") (name "Net-(LED174-C)") (class "Default")
      (node (ref "LED173") (pin "A") (pinfunction "A_A") (pintype "passive"))
      (node (ref "LED174") (pin "K") (pinfunction "C_K") (pintype "passive"))
    )
    (net (code "184") (name "Net-(LED175-C)") (class "Default")
      (node (ref "LED174") (pin "A") (pinfunction "A_A") (pintype "passive"))
      (node (ref "LED175") (pin "K") (pinfunction "C_K") (pintype "passive"))
    )
    (net (code "185") (name "Net-(LED176-C)") (class "Default")
      (node (ref "LED175") (pin "A") (pinfunction "A_A") (pintype "passive"))
      (node (ref "LED176") (pin "K") (pinfunction "C_K") (pintype "passive"))
    )
    (net (code "186") (name "Net-(LED178-C)") (class "Default")
      (node (ref "LED177") (pin "A") (pinfunction "A_A") (pintype "passive"))
      (node (ref "LED178") (pin "K") (pinfunction "C_K") (pintype "passive"))
    )
    (net (code "187") (name "Net-(LED179-C)") (class "Default")
      (node (ref "LED178") (pin "A") (pinfunction "A_A") (pintype "passive"))
      (node (ref "LED179") (pin "K") (pinfunction "C_K") (pintype "passive"))
    )
    (net (code "188") (name "Net-(LED180-C)") (class "Default")
      (node (ref "LED179") (pin "A") (pinfunction "A_A") (pintype "passive"))
      (node (ref "LED180") (pin "K") (pinfunction "C_K") (pintype "passive"))
    )
    (net (code "189") (name "Net-(LED181-C)") (class "Default")
      (node (ref "LED180") (pin "A") (pinfunction "A_A") (pintype "passive"))
      (node (ref "LED181") (pin "K") (pinfunction "C_K") (pintype "passive"))
    )
    (net (code "190") (name "Net-(LED182-C)") (class "Default")
      (node (ref "LED181") (pin "A") (pinfunction "A_A") (pintype "passive"))
      (node (ref "LED182") (pin "K") (pinfunction "C_K") (pintype "passive"))
    )
    (net (code "191") (name "Net-(LED183-C)") (class "Default")
      (node (ref "LED182") (pin "A") (pinfunction "A_A") (pintype "passive"))
      (node (ref "LED183") (pin "K") (pinfunction "C_K") (pintype "passive"))
    )
    (net (code "192") (name "Net-(LED184-C)") (class "Default")
      (node (ref "LED183") (pin "A") (pinfunction "A_A") (pintype "passive"))
      (node (ref "LED184") (pin "K") (pinfunction "C_K") (pintype "passive"))
    )
    (net (code "193") (name "Net-(LED185-C)") (class "Default")
      (node (ref "LED184") (pin "A") (pinfunction "A_A") (pintype "passive"))
      (node (ref "LED185") (pin "K") (pinfunction "C_K") (pintype "passive"))
    )
    (net (code "194") (name "Net-(LED186-C)") (class "Default")
      (node (ref "LED185") (pin "A") (pinfunction "A_A") (pintype "passive"))
      (node (ref "LED186") (pin "K") (pinfunction "C_K") (pintype "passive"))
    )
    (net (code "195") (name "Net-(LED187-C)") (class "Default")
      (node (ref "LED186") (pin "A") (pinfunction "A_A") (pintype "passive"))
      (node (ref "LED187") (pin "K") (pinfunction "C_K") (pintype "passive"))
    )
    (net (code "196") (name "Net-(LED188-C)") (class "Default")
      (node (ref "LED187") (pin "A") (pinfunction "A_A") (pintype "passive"))
      (node (ref "LED188") (pin "K") (pinfunction "C_K") (pintype "passive"))
    )
    (net (code "197") (name "Net-(LED189-C)") (class "Default")
      (node (ref "LED188") (pin "A") (pinfunction "A_A") (pintype "passive"))
      (node (ref "LED189") (pin "K") (pinfunction "C_K") (pintype "passive"))
    )
    (net (code "198") (name "Net-(LED190-C)") (class "Default")
      (node (ref "LED189") (pin "A") (pinfunction "A_A") (pintype "passive"))
      (node (ref "LED190") (pin "K") (pinfunction "C_K") (pintype "passive"))
    )
    (net (code "199") (name "Net-(LED191-C)") (class "Default")
      (node (ref "LED190") (pin "A") (pinfunction "A_A") (pintype "passive"))
      (node (ref "LED191") (pin "K") (pinfunction "C_K") (pintype "passive"))
    )
    (net (code "200") (name "Net-(LED192-C)") (class "Default")
      (node (ref "LED191") (pin "A") (pinfunction "A_A") (pintype "passive"))
      (node (ref "LED192") (pin "K") (pinfunction "C_K") (pintype "passive"))
    )
    (net (code "201") (name "Net-(LED193-C)") (class "Default")
      (node (ref "LED192") (pin "A") (pinfunction "A_A") (pintype "passive"))
      (node (ref "LED193") (pin "K") (pinfunction "C_K") (pintype "passive"))
    )
    (net (code "202") (name "Net-(LED194-C)") (class "Default")
      (node (ref "LED193") (pin "A") (pinfunction "A_A") (pintype "passive"))
      (node (ref "LED194") (pin "K") (pinfunction "C_K") (pintype "passive"))
    )
    (net (code "203") (name "Net-(LED195-C)") (class "Default")
      (node (ref "LED194") (pin "A") (pinfunction "A_A") (pintype "passive"))
      (node (ref "LED195") (pin "K") (pinfunction "C_K") (pintype "passive"))
    )
    (net (code "204") (name "Net-(LED197-C)") (class "Default")
      (node (ref "LED196") (pin "A") (pinfunction "A_A") (pintype "passive"))
      (node (ref "LED197") (pin "K") (pinfunction "C_K") (pintype "passive"))
    )
    (net (code "205") (name "Net-(LED198-C)") (class "Default")
      (node (ref "LED197") (pin "A") (pinfunction "A_A") (pintype "passive"))
      (node (ref "LED198") (pin "K") (pinfunction "C_K") (pintype "passive"))
    )
    (net (code "206") (name "Net-(LED199-C)") (class "Default")
      (node (ref "LED198") (pin "A") (pinfunction "A_A") (pintype "passive"))
      (node (ref "LED199") (pin "K") (pinfunction "C_K") (pintype "passive"))
    )
    (net (code "207") (name "Net-(LED200-C)") (class "Default")
      (node (ref "LED199") (pin "A") (pinfunction "A_A") (pintype "passive"))
      (node (ref "LED200") (pin "K") (pinfunction "C_K") (pintype "passive"))
    )
    (net (code "208") (name "Net-(LED201-C)") (class "Default")
      (node (ref "LED200") (pin "A") (pinfunction "A_A") (pintype "passive"))
      (node (ref "LED201") (pin "K") (pinfunction "C_K") (pintype "passive"))
    )
    (net (code "209") (name "Net-(LED202-C)") (class "Default")
      (node (ref "LED201") (pin "A") (pinfunction "A_A") (pintype "passive"))
      (node (ref "LED202") (pin "K") (pinfunction "C_K") (pintype "passive"))
    )
    (net (code "210") (name "Net-(LED203-C)") (class "Default")
      (node (ref "LED202") (pin "A") (pinfunction "A_A") (pintype "passive"))
      (node (ref "LED203") (pin "K") (pinfunction "C_K") (pintype "passive"))
    )
    (net (code "211") (name "Net-(LED204-C)") (class "Default")
      (node (ref "LED203") (pin "A") (pinfunction "A_A") (pintype "passive"))
      (node (ref "LED204") (pin "K") (pinfunction "C_K") (pintype "passive"))
    )
    (net (code "212") (name "Net-(LED205-C)") (class "Default")
      (node (ref "LED204") (pin "A") (pinfunction "A_A") (pintype "passive"))
      (node (ref "LED205") (pin "K") (pinfunction "C_K") (pintype "passive"))
    )
    (net (code "213") (name "Net-(LED206-C)") (class "Default")
      (node (ref "LED205") (pin "A") (pinfunction "A_A") (pintype "passive"))
      (node (ref "LED206") (pin "K") (pinfunction "C_K") (pintype "passive"))
    )
    (net (code "214") (name "Net-(LED207-C)") (class "Default")
      (node (ref "LED206") (pin "A") (pinfunction "A_A") (pintype "passive"))
      (node (ref "LED207") (pin "K") (pinfunction "C_K") (pintype "passive"))
    )
    (net (code "215") (name "Net-(LED208-C)") (class "Default")
      (node (ref "LED207") (pin "A") (pinfunction "A_A") (pintype "passive"))
      (node (ref "LED208") (pin "K") (pinfunction "C_K") (pintype "passive"))
    )
    (net (code "216") (name "Net-(LED209-C)") (class "Default")
      (node (ref "LED208") (pin "A") (pinfunction "A_A") (pintype "passive"))
      (node (ref "LED209") (pin "K") (pinfunction "C_K") (pintype "passive"))
    )
    (net (code "217") (name "Net-(LED210-C)") (class "Default")
      (node (ref "LED209") (pin "A") (pinfunction "A_A") (pintype "passive"))
      (node (ref "LED210") (pin "K") (pinfunction "C_K") (pintype "passive"))
    )
    (net (code "218") (name "Net-(LED211-C)") (class "Default")
      (node (ref "LED210") (pin "A") (pinfunction "A_A") (pintype "passive"))
      (node (ref "LED211") (pin "K") (pinfunction "C_K") (pintype "passive"))
    )
    (net (code "219") (name "Net-(LED212-C)") (class "Default")
      (node (ref "LED211") (pin "A") (pinfunction "A_A") (pintype "passive"))
      (node (ref "LED212") (pin "K") (pinfunction "C_K") (pintype "passive"))
    )
    (net (code "220") (name "Net-(LED213-C)") (class "Default")
      (node (ref "LED212") (pin "A") (pinfunction "A_A") (pintype "passive"))
      (node (ref "LED213") (pin "K") (pinfunction "C_K") (pintype "passive"))
    )
    (net (code "221") (name "Net-(LED214-C)") (class "Default")
      (node (ref "LED213") (pin "A") (pinfunction "A_A") (pintype "passive"))
      (node (ref "LED214") (pin "K") (pinfunction "C_K") (pintype "passive"))
    )
    (net (code "222") (name "Net-(LED215-C)") (class "Default")
      (node (ref "LED214") (pin "A") (pinfunction "A_A") (pintype "passive"))
      (node (ref "LED215") (pin "K") (pinfunction "C_K") (pintype "passive"))
    )
    (net (code "223") (name "Net-(LED217-C)") (class "Default")
      (node (ref "LED216") (pin "A") (pinfunction "A_A") (pintype "passive"))
      (node (ref "LED217") (pin "K") (pinfunction "C_K") (pintype "passive"))
    )
    (net (code "224") (name "Net-(LED218-C)") (class "Default")
      (node (ref "LED217") (pin "A") (pinfunction "A_A") (pintype "passive"))
      (node (ref "LED218") (pin "K") (pinfunction "C_K") (pintype "passive"))
    )
    (net (code "225") (name "Net-(LED219-C)") (class "Default")
      (node (ref "LED218") (pin "A") (pinfunction "A_A") (pintype "passive"))
      (node (ref "LED219") (pin "K") (pinfunction "C_K") (pintype "passive"))
    )
    (net (code "226") (name "Net-(LED220-C)") (class "Default")
      (node (ref "LED219") (pin "A") (pinfunction "A_A") (pintype "passive"))
      (node (ref "LED220") (pin "K") (pinfunction "C_K") (pintype "passive"))
    )
    (net (code "227") (name "Net-(LED221-C)") (class "Default")
      (node (ref "LED220") (pin "A") (pinfunction "A_A") (pintype "passive"))
      (node (ref "LED221") (pin "K") (pinfunction "C_K") (pintype "passive"))
    )
    (net (code "228") (name "Net-(LED222-C)") (class "Default")
      (node (ref "LED221") (pin "A") (pinfunction "A_A") (pintype "passive"))
      (node (ref "LED222") (pin "K") (pinfunction "C_K") (pintype "passive"))
    )
    (net (code "229") (name "Net-(LED223-C)") (class "Default")
      (node (ref "LED222") (pin "A") (pinfunction "A_A") (pintype "passive"))
      (node (ref "LED223") (pin "K") (pinfunction "C_K") (pintype "passive"))
    )
    (net (code "230") (name "Net-(LED224-C)") (class "Default")
      (node (ref "LED223") (pin "A") (pinfunction "A_A") (pintype "passive"))
      (node (ref "LED224") (pin "K") (pinfunction "C_K") (pintype "passive"))
    )
    (net (code "231") (name "Net-(LED225-C)") (class "Default")
      (node (ref "LED224") (pin "A") (pinfunction "A_A") (pintype "passive"))
      (node (ref "LED225") (pin "K") (pinfunction "C_K") (pintype "passive"))
    )
    (net (code "232") (name "Net-(LED226-C)") (class "Default")
      (node (ref "LED225") (pin "A") (pinfunction "A_A") (pintype "passive"))
      (node (ref "LED226") (pin "K") (pinfunction "C_K") (pintype "passive"))
    )
    (net (code "233") (name "Net-(LED227-C)") (class "Default")
      (node (ref "LED226") (pin "A") (pinfunction "A_A") (pintype "passive"))
      (node (ref "LED227") (pin "K") (pinfunction "C_K") (pintype "passive"))
    )
    (net (code "234") (name "Net-(LED228-C)") (class "Default")
      (node (ref "LED227") (pin "A") (pinfunction "A_A") (pintype "passive"))
      (node (ref "LED228") (pin "K") (pinfunction "C_K") (pintype "passive"))
    )
    (net (code "235") (name "Net-(LED229-C)") (class "Default")
      (node (ref "LED228") (pin "A") (pinfunction "A_A") (pintype "passive"))
      (node (ref "LED229") (pin "K") (pinfunction "C_K") (pintype "passive"))
    )
    (net (code "236") (name "Net-(LED230-C)") (class "Default")
      (node (ref "LED229") (pin "A") (pinfunction "A_A") (pintype "passive"))
      (node (ref "LED230") (pin "K") (pinfunction "C_K") (pintype "passive"))
    )
    (net (code "237") (name "Net-(LED231-C)") (class "Default")
      (node (ref "LED230") (pin "A") (pinfunction "A_A") (pintype "passive"))
      (node (ref "LED231") (pin "K") (pinfunction "C_K") (pintype "passive"))
    )
    (net (code "238") (name "Net-(LED232-C)") (class "Default")
      (node (ref "LED231") (pin "A") (pinfunction "A_A") (pintype "passive"))
      (node (ref "LED232") (pin "K") (pinfunction "C_K") (pintype "passive"))
    )
    (net (code "239") (name "Net-(LED233-C)") (class "Default")
      (node (ref "LED232") (pin "A") (pinfunction "A_A") (pintype "passive"))
      (node (ref "LED233") (pin "K") (pinfunction "C_K") (pintype "passive"))
    )
    (net (code "240") (name "Net-(LED234-C)") (class "Default")
      (node (ref "LED233") (pin "A") (pinfunction "A_A") (pintype "passive"))
      (node (ref "LED234") (pin "K") (pinfunction "C_K") (pintype "passive"))
    )
    (net (code "241") (name "Net-(LED236-C)") (class "Default")
      (node (ref "LED235") (pin "A") (pinfunction "A_A") (pintype "passive"))
      (node (ref "LED236") (pin "K") (pinfunction "C_K") (pintype "passive"))
    )
    (net (code "242") (name "Net-(LED237-C)") (class "Default")
      (node (ref "LED236") (pin "A") (pinfunction "A_A") (pintype "passive"))
      (node (ref "LED237") (pin "K") (pinfunction "C_K") (pintype "passive"))
    )
    (net (code "243") (name "Net-(LED238-C)") (class "Default")
      (node (ref "LED237") (pin "A") (pinfunction "A_A") (pintype "passive"))
      (node (ref "LED238") (pin "K") (pinfunction "C_K") (pintype "passive"))
    )
    (net (code "244") (name "Net-(LED239-C)") (class "Default")
      (node (ref "LED238") (pin "A") (pinfunction "A_A") (pintype "passive"))
      (node (ref "LED239") (pin "K") (pinfunction "C_K") (pintype "passive"))
    )
    (net (code "245") (name "Net-(LED240-C)") (class "Default")
      (node (ref "LED239") (pin "A") (pinfunction "A_A") (pintype "passive"))
      (node (ref "LED240") (pin "K") (pinfunction "C_K") (pintype "passive"))
    )
    (net (code "246") (name "Net-(LED241-C)") (class "Default")
      (node (ref "LED240") (pin "A") (pinfunction "A_A") (pintype "passive"))
      (node (ref "LED241") (pin "K") (pinfunction "C_K") (pintype "passive"))
    )
    (net (code "247") (name "Net-(LED242-C)") (class "Default")
      (node (ref "LED241") (pin "A") (pinfunction "A_A") (pintype "passive"))
      (node (ref "LED242") (pin "K") (pinfunction "C_K") (pintype "passive"))
    )
    (net (code "248") (name "Net-(LED243-C)") (class "Default")
      (node (ref "LED242") (pin "A") (pinfunction "A_A") (pintype "passive"))
      (node (ref "LED243") (pin "K") (pinfunction "C_K") (pintype "passive"))
    )
    (net (code "249") (name "Net-(LED244-C)") (class "Default")
      (node (ref "LED243") (pin "A") (pinfunction "A_A") (pintype "passive"))
      (node (ref "LED244") (pin "K") (pinfunction "C_K") (pintype "passive"))
    )
    (net (code "250") (name "Net-(LED245-C)") (class "Default")
      (node (ref "LED244") (pin "A") (pinfunction "A_A") (pintype "passive"))
      (node (ref "LED245") (pin "K") (pinfunction "C_K") (pintype "passive"))
    )
    (net (code "251") (name "Net-(LED246-C)") (class "Default")
      (node (ref "LED245") (pin "A") (pinfunction "A_A") (pintype "passive"))
      (node (ref "LED246") (pin "K") (pinfunction "C_K") (pintype "passive"))
    )
    (net (code "252") (name "Net-(LED247-C)") (class "Default")
      (node (ref "LED246") (pin "A") (pinfunction "A_A") (pintype "passive"))
      (node (ref "LED247") (pin "K") (pinfunction "C_K") (pintype "passive"))
    )
    (net (code "253") (name "Net-(LED248-C)") (class "Default")
      (node (ref "LED247") (pin "A") (pinfunction "A_A") (pintype "passive"))
      (node (ref "LED248") (pin "K") (pinfunction "C_K") (pintype "passive"))
    )
    (net (code "254") (name "Net-(LED249-C)") (class "Default")
      (node (ref "LED248") (pin "A") (pinfunction "A_A") (pintype "passive"))
      (node (ref "LED249") (pin "K") (pinfunction "C_K") (pintype "passive"))
    )
    (net (code "255") (name "Net-(LED250-C)") (class "Default")
      (node (ref "LED249") (pin "A") (pinfunction "A_A") (pintype "passive"))
      (node (ref "LED250") (pin "K") (pinfunction "C_K") (pintype "passive"))
    )
    (net (code "256") (name "Net-(LED251-C)") (class "Default")
      (node (ref "LED250") (pin "A") (pinfunction "A_A") (pintype "passive"))
      (node (ref "LED251") (pin "K") (pinfunction "C_K") (pintype "passive"))
    )
    (net (code "257") (name "Net-(LED252-C)") (class "Default")
      (node (ref "LED251") (pin "A") (pinfunction "A_A") (pintype "passive"))
      (node (ref "LED252") (pin "K") (pinfunction "C_K") (pintype "passive"))
    )
    (net (code "258") (name "Net-(LED253-C)") (class "Default")
      (node (ref "LED252") (pin "A") (pinfunction "A_A") (pintype "passive"))
      (node (ref "LED253") (pin "K") (pinfunction "C_K") (pintype "passive"))
    )
    (net (code "259") (name "Net-(LED254-C)") (class "Default")
      (node (ref "LED253") (pin "A") (pinfunction "A_A") (pintype "passive"))
      (node (ref "LED254") (pin "K") (pinfunction "C_K") (pintype "passive"))
    )
    (net (code "260") (name "Net-(LED256-C)") (class "Default")
      (node (ref "LED255") (pin "A") (pinfunction "A_A") (pintype "passive"))
      (node (ref "LED256") (pin "K") (pinfunction "C_K") (pintype "passive"))
    )
    (net (code "261") (name "Net-(LED257-C)") (class "Default")
      (node (ref "LED256") (pin "A") (pinfunction "A_A") (pintype "passive"))
      (node (ref "LED257") (pin "K") (pinfunction "C_K") (pintype "passive"))
    )
    (net (code "262") (name "Net-(LED258-C)") (class "Default")
      (node (ref "LED257") (pin "A") (pinfunction "A_A") (pintype "passive"))
      (node (ref "LED258") (pin "K") (pinfunction "C_K") (pintype "passive"))
    )
    (net (code "263") (name "Net-(LED259-C)") (class "Default")
      (node (ref "LED258") (pin "A") (pinfunction "A_A") (pintype "passive"))
      (node (ref "LED259") (pin "K") (pinfunction "C_K") (pintype "passive"))
    )
    (net (code "264") (name "Net-(LED260-C)") (class "Default")
      (node (ref "LED259") (pin "A") (pinfunction "A_A") (pintype "passive"))
      (node (ref "LED260") (pin "K") (pinfunction "C_K") (pintype "passive"))
    )
    (net (code "265") (name "Net-(LED261-C)") (class "Default")
      (node (ref "LED260") (pin "A") (pinfunction "A_A") (pintype "passive"))
      (node (ref "LED261") (pin "K") (pinfunction "C_K") (pintype "passive"))
    )
    (net (code "266") (name "Net-(LED262-C)") (class "Default")
      (node (ref "LED261") (pin "A") (pinfunction "A_A") (pintype "passive"))
      (node (ref "LED262") (pin "K") (pinfunction "C_K") (pintype "passive"))
    )
    (net (code "267") (name "Net-(LED263-C)") (class "Default")
      (node (ref "LED262") (pin "A") (pinfunction "A_A") (pintype "passive"))
      (node (ref "LED263") (pin "K") (pinfunction "C_K") (pintype "passive"))
    )
    (net (code "268") (name "Net-(LED264-C)") (class "Default")
      (node (ref "LED263") (pin "A") (pinfunction "A_A") (pintype "passive"))
      (node (ref "LED264") (pin "K") (pinfunction "C_K") (pintype "passive"))
    )
    (net (code "269") (name "Net-(LED265-C)") (class "Default")
      (node (ref "LED264") (pin "A") (pinfunction "A_A") (pintype "passive"))
      (node (ref "LED265") (pin "K") (pinfunction "C_K") (pintype "passive"))
    )
    (net (code "270") (name "Net-(LED266-C)") (class "Default")
      (node (ref "LED265") (pin "A") (pinfunction "A_A") (pintype "passive"))
      (node (ref "LED266") (pin "K") (pinfunction "C_K") (pintype "passive"))
    )
    (net (code "271") (name "Net-(LED267-C)") (class "Default")
      (node (ref "LED266") (pin "A") (pinfunction "A_A") (pintype "passive"))
      (node (ref "LED267") (pin "K") (pinfunction "C_K") (pintype "passive"))
    )
    (net (code "272") (name "Net-(LED268-C)") (class "Default")
      (node (ref "LED267") (pin "A") (pinfunction "A_A") (pintype "passive"))
      (node (ref "LED268") (pin "K") (pinfunction "C_K") (pintype "passive"))
    )
    (net (code "273") (name "Net-(LED269-C)") (class "Default")
      (node (ref "LED268") (pin "A") (pinfunction "A_A") (pintype "passive"))
      (node (ref "LED269") (pin "K") (pinfunction "C_K") (pintype "passive"))
    )
    (net (code "274") (name "Net-(LED270-C)") (class "Default")
      (node (ref "LED269") (pin "A") (pinfunction "A_A") (pintype "passive"))
      (node (ref "LED270") (pin "K") (pinfunction "C_K") (pintype "passive"))
    )
    (net (code "275") (name "Net-(LED271-C)") (class "Default")
      (node (ref "LED270") (pin "A") (pinfunction "A_A") (pintype "passive"))
      (node (ref "LED271") (pin "K") (pinfunction "C_K") (pintype "passive"))
    )
    (net (code "276") (name "Net-(LED272-C)") (class "Default")
      (node (ref "LED271") (pin "A") (pinfunction "A_A") (pintype "passive"))
      (node (ref "LED272") (pin "K") (pinfunction "C_K") (pintype "passive"))
    )
    (net (code "277") (name "Net-(LED273-C)") (class "Default")
      (node (ref "LED272") (pin "A") (pinfunction "A_A") (pintype "passive"))
      (node (ref "LED273") (pin "K") (pinfunction "C_K") (pintype "passive"))
    )
    (net (code "278") (name "Net-(LED275-C)") (class "Default")
      (node (ref "LED274") (pin "A") (pinfunction "A_A") (pintype "passive"))
      (node (ref "LED275") (pin "K") (pinfunction "C_K") (pintype "passive"))
    )
    (net (code "279") (name "Net-(LED276-C)") (class "Default")
      (node (ref "LED275") (pin "A") (pinfunction "A_A") (pintype "passive"))
      (node (ref "LED276") (pin "K") (pinfunction "C_K") (pintype "passive"))
    )
    (net (code "280") (name "Net-(LED277-C)") (class "Default")
      (node (ref "LED276") (pin "A") (pinfunction "A_A") (pintype "passive"))
      (node (ref "LED277") (pin "K") (pinfunction "C_K") (pintype "passive"))
    )
    (net (code "281") (name "Net-(LED278-C)") (class "Default")
      (node (ref "LED277") (pin "A") (pinfunction "A_A") (pintype "passive"))
      (node (ref "LED278") (pin "K") (pinfunction "C_K") (pintype "passive"))
    )
    (net (code "282") (name "Net-(LED279-C)") (class "Default")
      (node (ref "LED278") (pin "A") (pinfunction "A_A") (pintype "passive"))
      (node (ref "LED279") (pin "K") (pinfunction "C_K") (pintype "passive"))
    )
    (net (code "283") (name "Net-(LED280-C)") (class "Default")
      (node (ref "LED279") (pin "A") (pinfunction "A_A") (pintype "passive"))
      (node (ref "LED280") (pin "K") (pinfunction "C_K") (pintype "passive"))
    )
    (net (code "284") (name "Net-(LED281-C)") (class "Default")
      (node (ref "LED280") (pin "A") (pinfunction "A_A") (pintype "passive"))
      (node (ref "LED281") (pin "K") (pinfunction "C_K") (pintype "passive"))
    )
    (net (code "285") (name "Net-(LED282-C)") (class "Default")
      (node (ref "LED281") (pin "A") (pinfunction "A_A") (pintype "passive"))
      (node (ref "LED282") (pin "K") (pinfunction "C_K") (pintype "passive"))
    )
    (net (code "286") (name "Net-(LED283-C)") (class "Default")
      (node (ref "LED282") (pin "A") (pinfunction "A_A") (pintype "passive"))
      (node (ref "LED283") (pin "K") (pinfunction "C_K") (pintype "passive"))
    )
    (net (code "287") (name "Net-(LED284-C)") (class "Default")
      (node (ref "LED283") (pin "A") (pinfunction "A_A") (pintype "passive"))
      (node (ref "LED284") (pin "K") (pinfunction "C_K") (pintype "passive"))
    )
    (net (code "288") (name "Net-(LED285-C)") (class "Default")
      (node (ref "LED284") (pin "A") (pinfunction "A_A") (pintype "passive"))
      (node (ref "LED285") (pin "K") (pinfunction "C_K") (pintype "passive"))
    )
    (net (code "289") (name "Net-(LED286-C)") (class "Default")
      (node (ref "LED285") (pin "A") (pinfunction "A_A") (pintype "passive"))
      (node (ref "LED286") (pin "K") (pinfunction "C_K") (pintype "passive"))
    )
    (net (code "290") (name "Net-(LED287-C)") (class "Default")
      (node (ref "LED286") (pin "A") (pinfunction "A_A") (pintype "passive"))
      (node (ref "LED287") (pin "K") (pinfunction "C_K") (pintype "passive"))
    )
    (net (code "291") (name "Net-(LED288-C)") (class "Default")
      (node (ref "LED287") (pin "A") (pinfunction "A_A") (pintype "passive"))
      (node (ref "LED288") (pin "K") (pinfunction "C_K") (pintype "passive"))
    )
    (net (code "292") (name "Net-(LED289-C)") (class "Default")
      (node (ref "LED288") (pin "A") (pinfunction "A_A") (pintype "passive"))
      (node (ref "LED289") (pin "K") (pinfunction "C_K") (pintype "passive"))
    )
    (net (code "293") (name "Net-(LED290-C)") (class "Default")
      (node (ref "LED289") (pin "A") (pinfunction "A_A") (pintype "passive"))
      (node (ref "LED290") (pin "K") (pinfunction "C_K") (pintype "passive"))
    )
    (net (code "294") (name "Net-(LED291-C)") (class "Default")
      (node (ref "LED290") (pin "A") (pinfunction "A_A") (pintype "passive"))
      (node (ref "LED291") (pin "K") (pinfunction "C_K") (pintype "passive"))
    )
    (net (code "295") (name "Net-(LED292-C)") (class "Default")
      (node (ref "LED291") (pin "A") (pinfunction "A_A") (pintype "passive"))
      (node (ref "LED292") (pin "K") (pinfunction "C_K") (pintype "passive"))
    )
    (net (code "296") (name "Net-(LED293-C)") (class "Default")
      (node (ref "LED292") (pin "A") (pinfunction "A_A") (pintype "passive"))
      (node (ref "LED293") (pin "K") (pinfunction "C_K") (pintype "passive"))
    )
    (net (code "297") (name "Net-(LED295-C)") (class "Default")
      (node (ref "LED294") (pin "A") (pinfunction "A_A") (pintype "passive"))
      (node (ref "LED295") (pin "K") (pinfunction "C_K") (pintype "passive"))
    )
    (net (code "298") (name "Net-(LED296-C)") (class "Default")
      (node (ref "LED295") (pin "A") (pinfunction "A_A") (pintype "passive"))
      (node (ref "LED296") (pin "K") (pinfunction "C_K") (pintype "passive"))
    )
    (net (code "299") (name "Net-(LED297-C)") (class "Default")
      (node (ref "LED296") (pin "A") (pinfunction "A_A") (pintype "passive"))
      (node (ref "LED297") (pin "K") (pinfunction "C_K") (pintype "passive"))
    )
    (net (code "300") (name "Net-(LED298-C)") (class "Default")
      (node (ref "LED297") (pin "A") (pinfunction "A_A") (pintype "passive"))
      (node (ref "LED298") (pin "K") (pinfunction "C_K") (pintype "passive"))
    )
    (net (code "301") (name "Net-(LED299-C)") (class "Default")
      (node (ref "LED298") (pin "A") (pinfunction "A_A") (pintype "passive"))
      (node (ref "LED299") (pin "K") (pinfunction "C_K") (pintype "passive"))
    )
    (net (code "302") (name "Net-(LED300-C)") (class "Default")
      (node (ref "LED299") (pin "A") (pinfunction "A_A") (pintype "passive"))
      (node (ref "LED300") (pin "K") (pinfunction "C_K") (pintype "passive"))
    )
    (net (code "303") (name "Net-(LED301-C)") (class "Default")
      (node (ref "LED300") (pin "A") (pinfunction "A_A") (pintype "passive"))
      (node (ref "LED301") (pin "K") (pinfunction "C_K") (pintype "passive"))
    )
    (net (code "304") (name "Net-(LED302-C)") (class "Default")
      (node (ref "LED301") (pin "A") (pinfunction "A_A") (pintype "passive"))
      (node (ref "LED302") (pin "K") (pinfunction "C_K") (pintype "passive"))
    )
    (net (code "305") (name "Net-(LED303-C)") (class "Default")
      (node (ref "LED302") (pin "A") (pinfunction "A_A") (pintype "passive"))
      (node (ref "LED303") (pin "K") (pinfunction "C_K") (pintype "passive"))
    )
    (net (code "306") (name "Net-(LED304-C)") (class "Default")
      (node (ref "LED303") (pin "A") (pinfunction "A_A") (pintype "passive"))
      (node (ref "LED304") (pin "K") (pinfunction "C_K") (pintype "passive"))
    )
    (net (code "307") (name "Net-(LED305-C)") (class "Default")
      (node (ref "LED304") (pin "A") (pinfunction "A_A") (pintype "passive"))
      (node (ref "LED305") (pin "K") (pinfunction "C_K") (pintype "passive"))
    )
    (net (code "308") (name "Net-(LED306-C)") (class "Default")
      (node (ref "LED305") (pin "A") (pinfunction "A_A") (pintype "passive"))
      (node (ref "LED306") (pin "K") (pinfunction "C_K") (pintype "passive"))
    )
    (net (code "309") (name "Net-(LED307-C)") (class "Default")
      (node (ref "LED306") (pin "A") (pinfunction "A_A") (pintype "passive"))
      (node (ref "LED307") (pin "K") (pinfunction "C_K") (pintype "passive"))
    )
    (net (code "310") (name "Net-(LED308-C)") (class "Default")
      (node (ref "LED307") (pin "A") (pinfunction "A_A") (pintype "passive"))
      (node (ref "LED308") (pin "K") (pinfunction "C_K") (pintype "passive"))
    )
    (net (code "311") (name "Net-(LED309-C)") (class "Default")
      (node (ref "LED308") (pin "A") (pinfunction "A_A") (pintype "passive"))
      (node (ref "LED309") (pin "K") (pinfunction "C_K") (pintype "passive"))
    )
    (net (code "312") (name "Net-(LED310-C)") (class "Default")
      (node (ref "LED309") (pin "A") (pinfunction "A_A") (pintype "passive"))
      (node (ref "LED310") (pin "K") (pinfunction "C_K") (pintype "passive"))
    )
    (net (code "313") (name "Net-(LED311-C)") (class "Default")
      (node (ref "LED310") (pin "A") (pinfunction "A_A") (pintype "passive"))
      (node (ref "LED311") (pin "K") (pinfunction "C_K") (pintype "passive"))
    )
    (net (code "314") (name "Net-(LED312-C)") (class "Default")
      (node (ref "LED311") (pin "A") (pinfunction "A_A") (pintype "passive"))
      (node (ref "LED312") (pin "K") (pinfunction "C_K") (pintype "passive"))
    )
    (net (code "315") (name "Net-(LED314-C)") (class "Default")
      (node (ref "LED313") (pin "A") (pinfunction "A_A") (pintype "passive"))
      (node (ref "LED314") (pin "K") (pinfunction "C_K") (pintype "passive"))
    )
    (net (code "316") (name "Net-(LED315-C)") (class "Default")
      (node (ref "LED314") (pin "A") (pinfunction "A_A") (pintype "passive"))
      (node (ref "LED315") (pin "K") (pinfunction "C_K") (pintype "passive"))
    )
    (net (code "317") (name "Net-(LED316-C)") (class "Default")
      (node (ref "LED315") (pin "A") (pinfunction "A_A") (pintype "passive"))
      (node (ref "LED316") (pin "K") (pinfunction "C_K") (pintype "passive"))
    )
    (net (code "318") (name "Net-(LED317-C)") (class "Default")
      (node (ref "LED316") (pin "A") (pinfunction "A_A") (pintype "passive"))
      (node (ref "LED317") (pin "K") (pinfunction "C_K") (pintype "passive"))
    )
    (net (code "319") (name "Net-(LED318-C)") (class "Default")
      (node (ref "LED317") (pin "A") (pinfunction "A_A") (pintype "passive"))
      (node (ref "LED318") (pin "K") (pinfunction "C_K") (pintype "passive"))
    )
    (net (code "320") (name "Net-(LED319-C)") (class "Default")
      (node (ref "LED318") (pin "A") (pinfunction "A_A") (pintype "passive"))
      (node (ref "LED319") (pin "K") (pinfunction "C_K") (pintype "passive"))
    )
    (net (code "321") (name "Net-(LED320-C)") (class "Default")
      (node (ref "LED319") (pin "A") (pinfunction "A_A") (pintype "passive"))
      (node (ref "LED320") (pin "K") (pinfunction "C_K") (pintype "passive"))
    )
    (net (code "322") (name "Net-(LED321-C)") (class "Default")
      (node (ref "LED320") (pin "A") (pinfunction "A_A") (pintype "passive"))
      (node (ref "LED321") (pin "K") (pinfunction "C_K") (pintype "passive"))
    )
    (net (code "323") (name "Net-(LED322-C)") (class "Default")
      (node (ref "LED321") (pin "A") (pinfunction "A_A") (pintype "passive"))
      (node (ref "LED322") (pin "K") (pinfunction "C_K") (pintype "passive"))
    )
    (net (code "324") (name "Net-(LED323-C)") (class "Default")
      (node (ref "LED322") (pin "A") (pinfunction "A_A") (pintype "passive"))
      (node (ref "LED323") (pin "K") (pinfunction "C_K") (pintype "passive"))
    )
    (net (code "325") (name "Net-(LED324-C)") (class "Default")
      (node (ref "LED323") (pin "A") (pinfunction "A_A") (pintype "passive"))
      (node (ref "LED324") (pin "K") (pinfunction "C_K") (pintype "passive"))
    )
    (net (code "326") (name "Net-(LED325-C)") (class "Default")
      (node (ref "LED324") (pin "A") (pinfunction "A_A") (pintype "passive"))
      (node (ref "LED325") (pin "K") (pinfunction "C_K") (pintype "passive"))
    )
    (net (code "327") (name "Net-(LED326-C)") (class "Default")
      (node (ref "LED325") (pin "A") (pinfunction "A_A") (pintype "passive"))
      (node (ref "LED326") (pin "K") (pinfunction "C_K") (pintype "passive"))
    )
    (net (code "328") (name "Net-(LED327-C)") (class "Default")
      (node (ref "LED326") (pin "A") (pinfunction "A_A") (pintype "passive"))
      (node (ref "LED327") (pin "K") (pinfunction "C_K") (pintype "passive"))
    )
    (net (code "329") (name "Net-(LED328-C)") (class "Default")
      (node (ref "LED327") (pin "A") (pinfunction "A_A") (pintype "passive"))
      (node (ref "LED328") (pin "K") (pinfunction "C_K") (pintype "passive"))
    )
    (net (code "330") (name "Net-(LED329-C)") (class "Default")
      (node (ref "LED328") (pin "A") (pinfunction "A_A") (pintype "passive"))
      (node (ref "LED329") (pin "K") (pinfunction "C_K") (pintype "passive"))
    )
    (net (code "331") (name "Net-(LED330-C)") (class "Default")
      (node (ref "LED329") (pin "A") (pinfunction "A_A") (pintype "passive"))
      (node (ref "LED330") (pin "K") (pinfunction "C_K") (pintype "passive"))
    )
    (net (code "332") (name "Net-(LED331-C)") (class "Default")
      (node (ref "LED330") (pin "A") (pinfunction "A_A") (pintype "passive"))
      (node (ref "LED331") (pin "K") (pinfunction "C_K") (pintype "passive"))
    )
    (net (code "333") (name "Net-(LED332-C)") (class "Default")
      (node (ref "LED331") (pin "A") (pinfunction "A_A") (pintype "passive"))
      (node (ref "LED332") (pin "K") (pinfunction "C_K") (pintype "passive"))
    )
    (net (code "334") (name "VCC") (class "Default")
      (node (ref "D1") (pin "A") (pinfunction "A_A") (pintype "passive"))
      (node (ref "D10") (pin "A") (pinfunction "A_A") (pintype "passive"))
      (node (ref "D11") (pin "A") (pinfunction "A_A") (pintype "passive"))
      (node (ref "D12") (pin "A") (pinfunction "A_A") (pintype "passive"))
      (node (ref "D13") (pin "A") (pinfunction "A_A") (pintype "passive"))
      (node (ref "D14") (pin "A") (pinfunction "A_A") (pintype "passive"))
      (node (ref "D15") (pin "A") (pinfunction "A_A") (pintype "passive"))
      (node (ref "D16") (pin "A") (pinfunction "A_A") (pintype "passive"))
      (node (ref "D17") (pin "A") (pinfunction "A_A") (pintype "passive"))
      (node (ref "D2") (pin "A") (pinfunction "A_A") (pintype "passive"))
      (node (ref "D3") (pin "A") (pinfunction "A_A") (pintype "passive"))
      (node (ref "D4") (pin "A") (pinfunction "A_A") (pintype "passive"))
      (node (ref "D5") (pin "A") (pinfunction "A_A") (pintype "passive"))
      (node (ref "D6") (pin "A") (pinfunction "A_A") (pintype "passive"))
      (node (ref "D7") (pin "A") (pinfunction "A_A") (pintype "passive"))
      (node (ref "D8") (pin "A") (pinfunction "A_A") (pintype "passive"))
      (node (ref "D9") (pin "A") (pinfunction "A_A") (pintype "passive"))
      (node (ref "VCC") (pin "1") (pinfunction "P_1") (pintype "passive"))
    )
  )
)
